# p2_half_bridge.net
KiCad netlist of a schematic drawn in Altium Designer
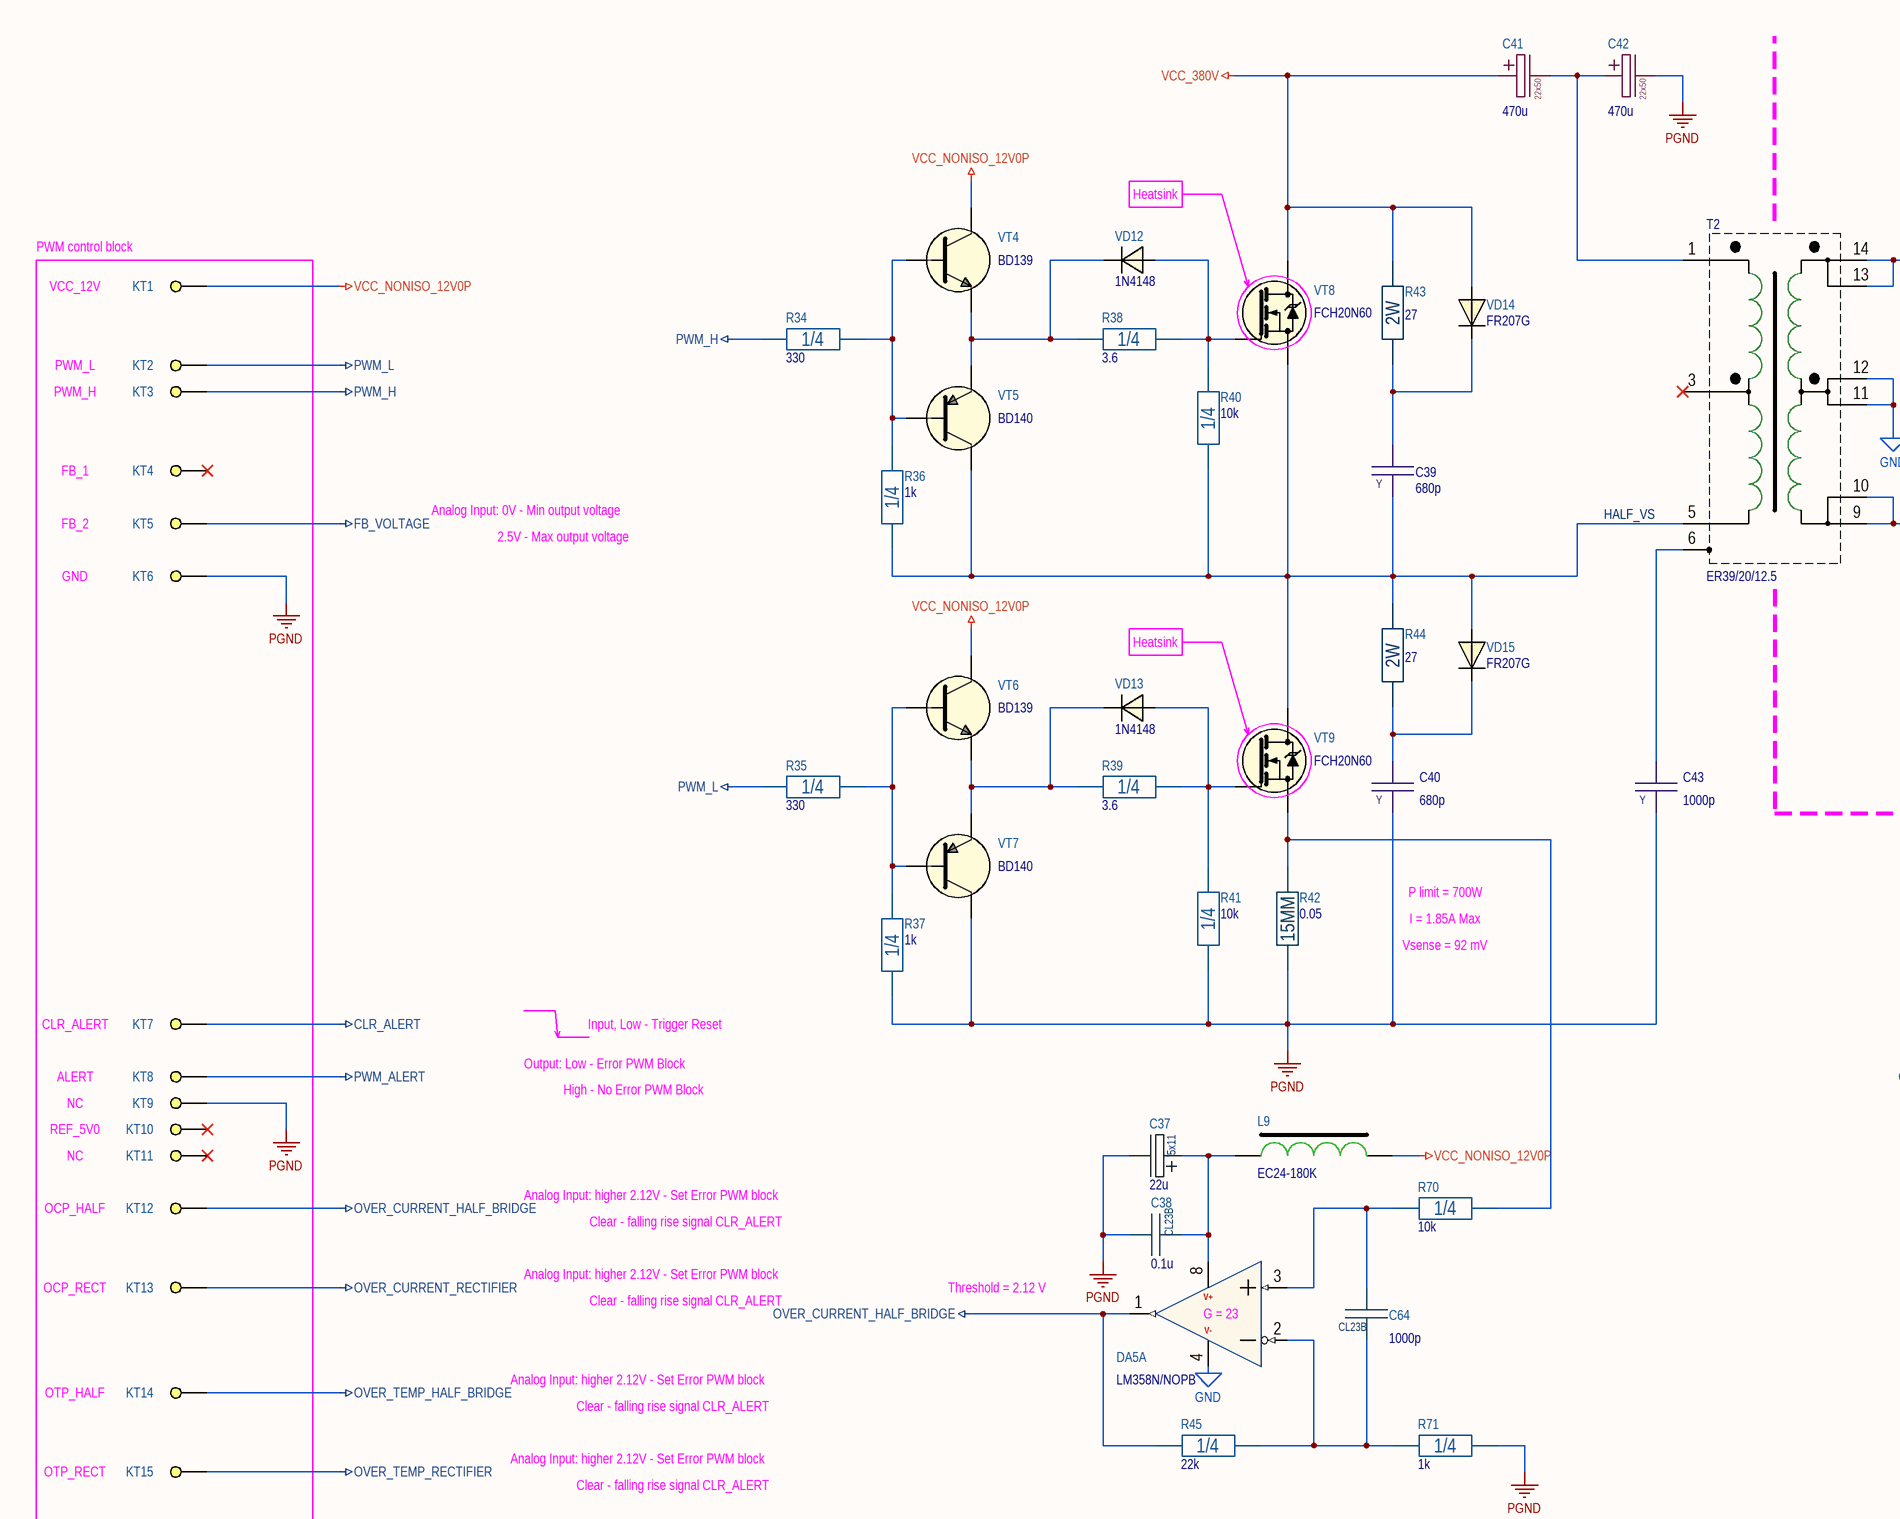
[diagram p0: p2_half_bridge.SchDoc, top left]
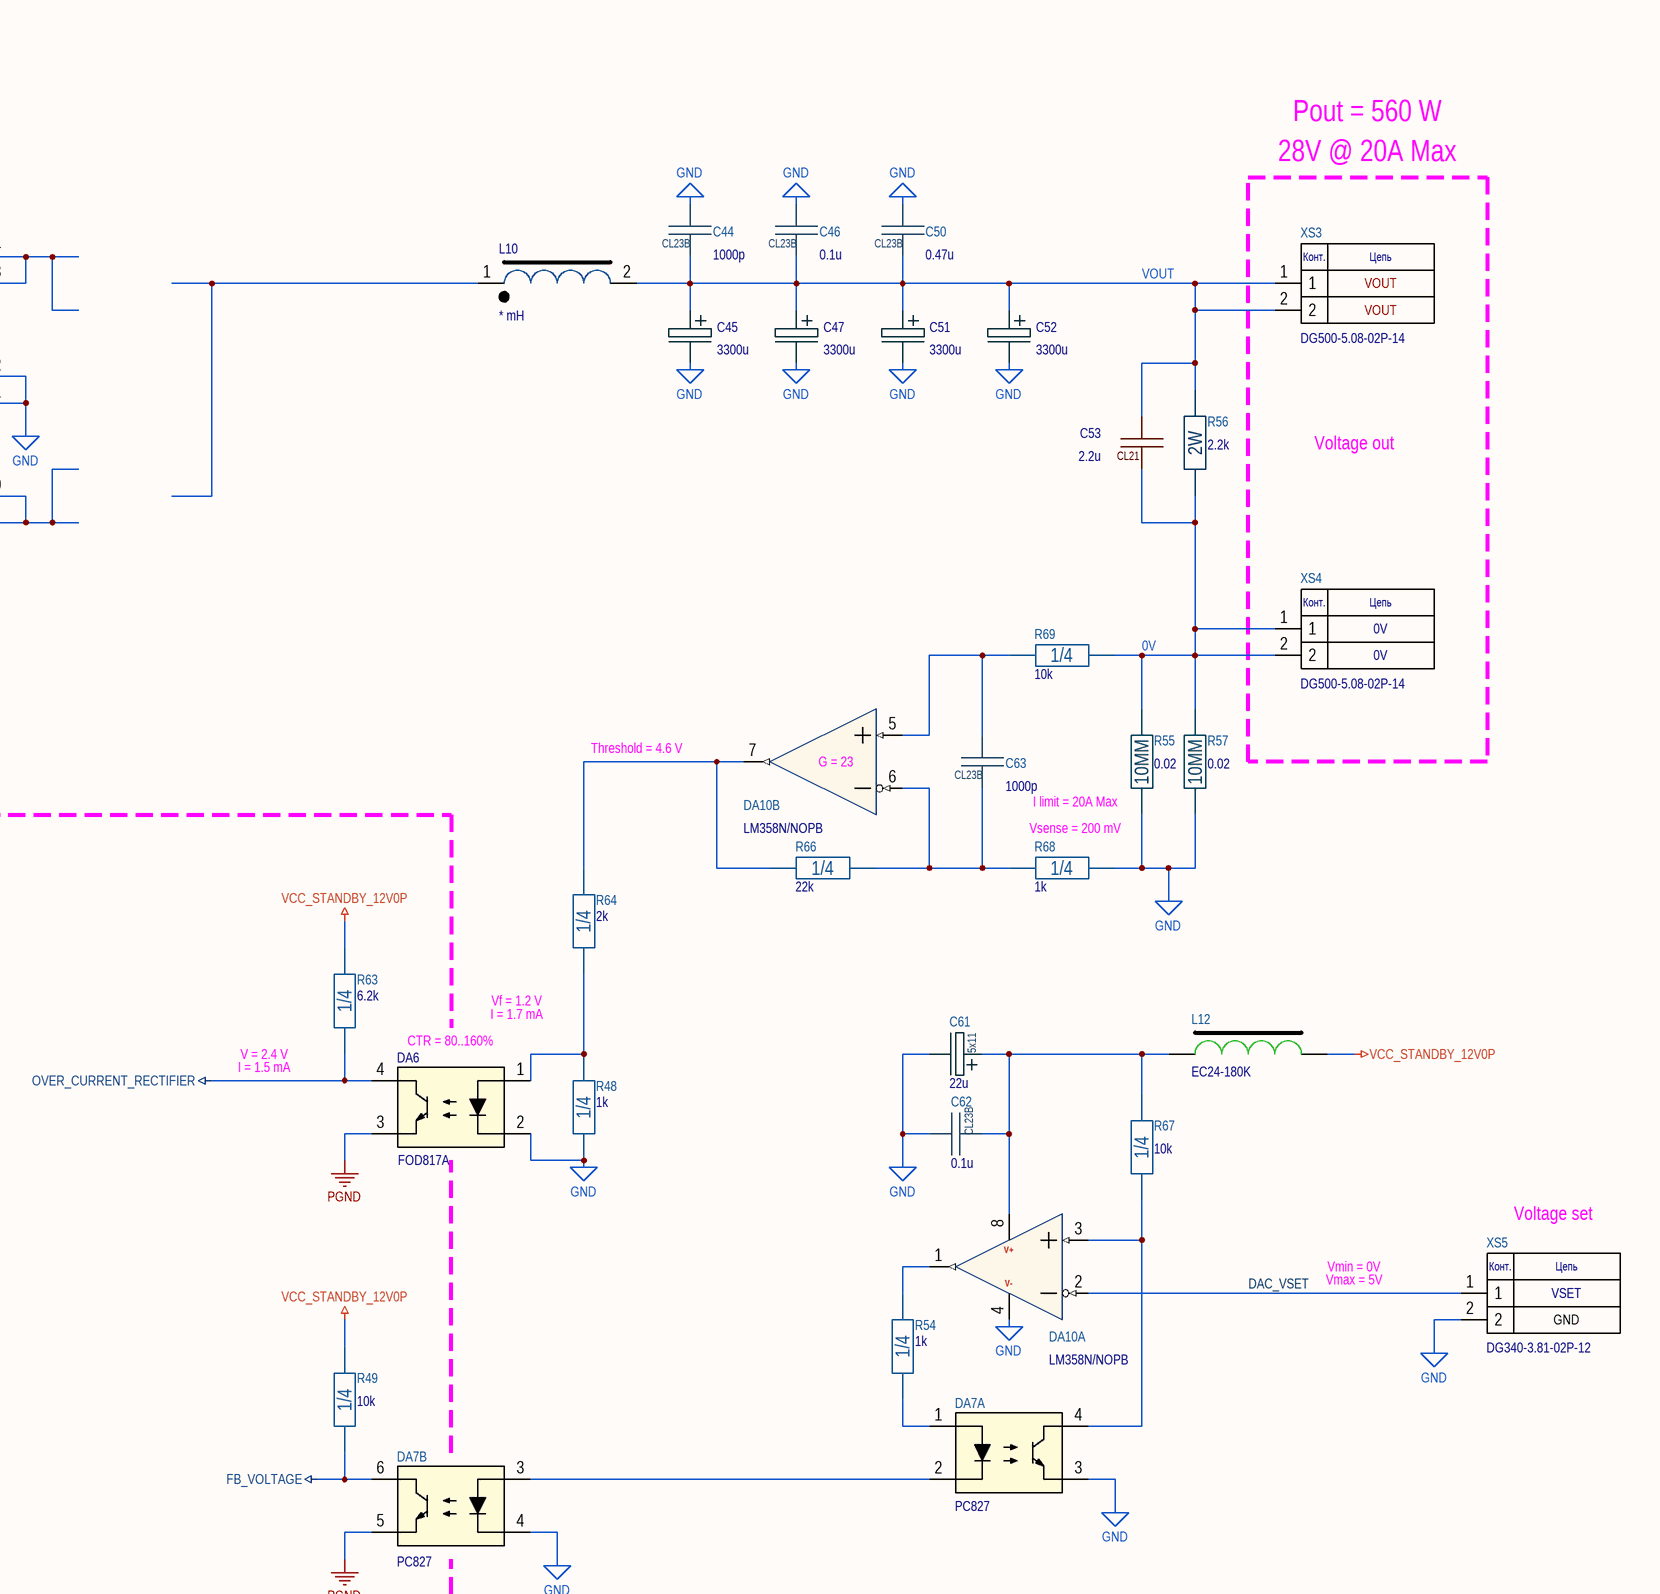
[diagram p1: p2_half_bridge.SchDoc, top right]
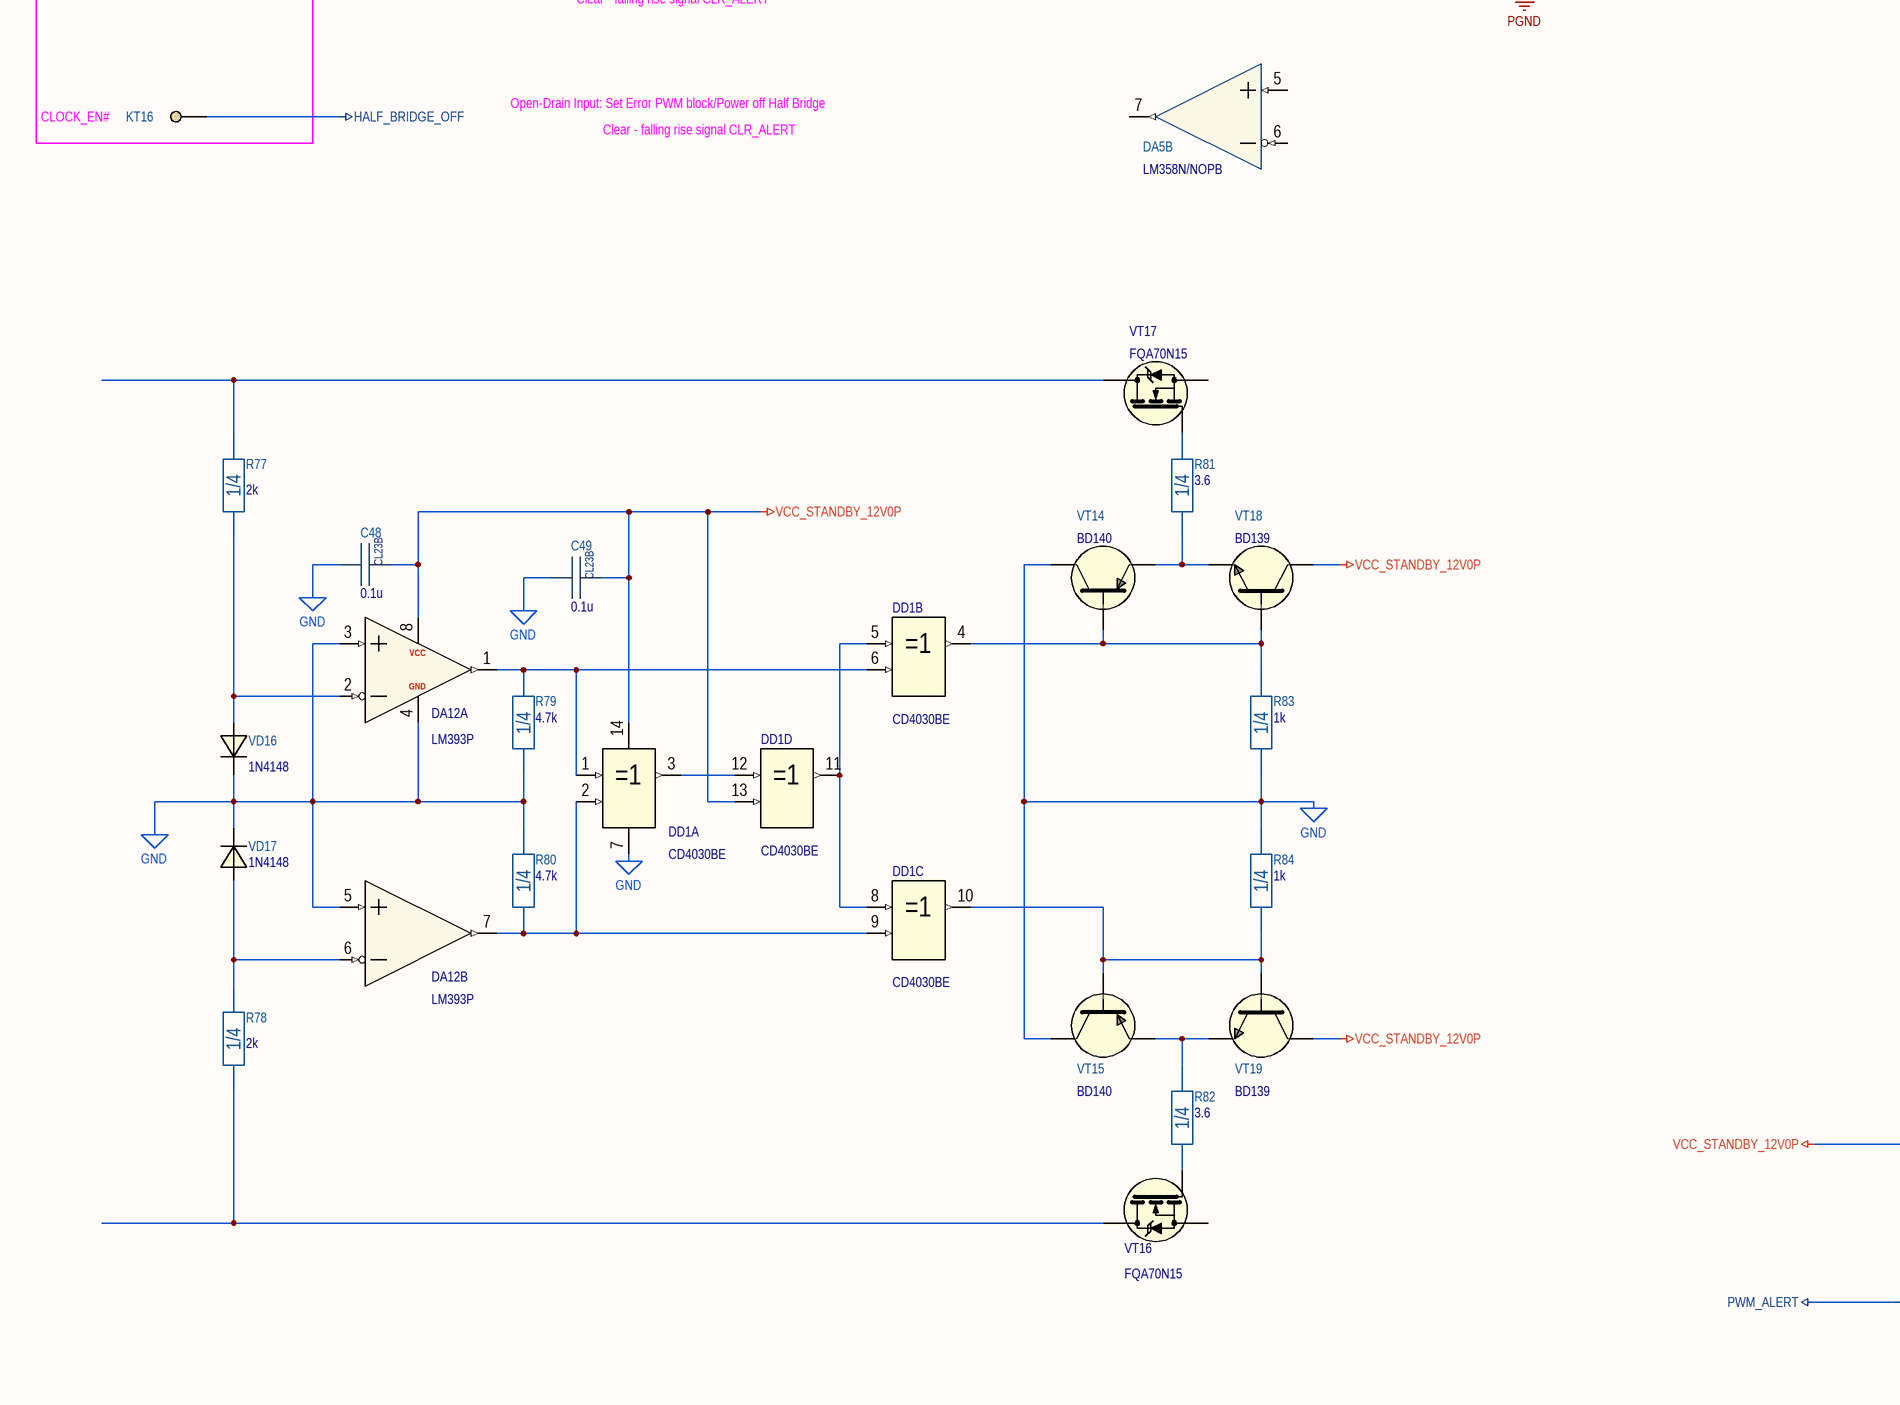
[diagram p2: p2_half_bridge.SchDoc, bottom left]
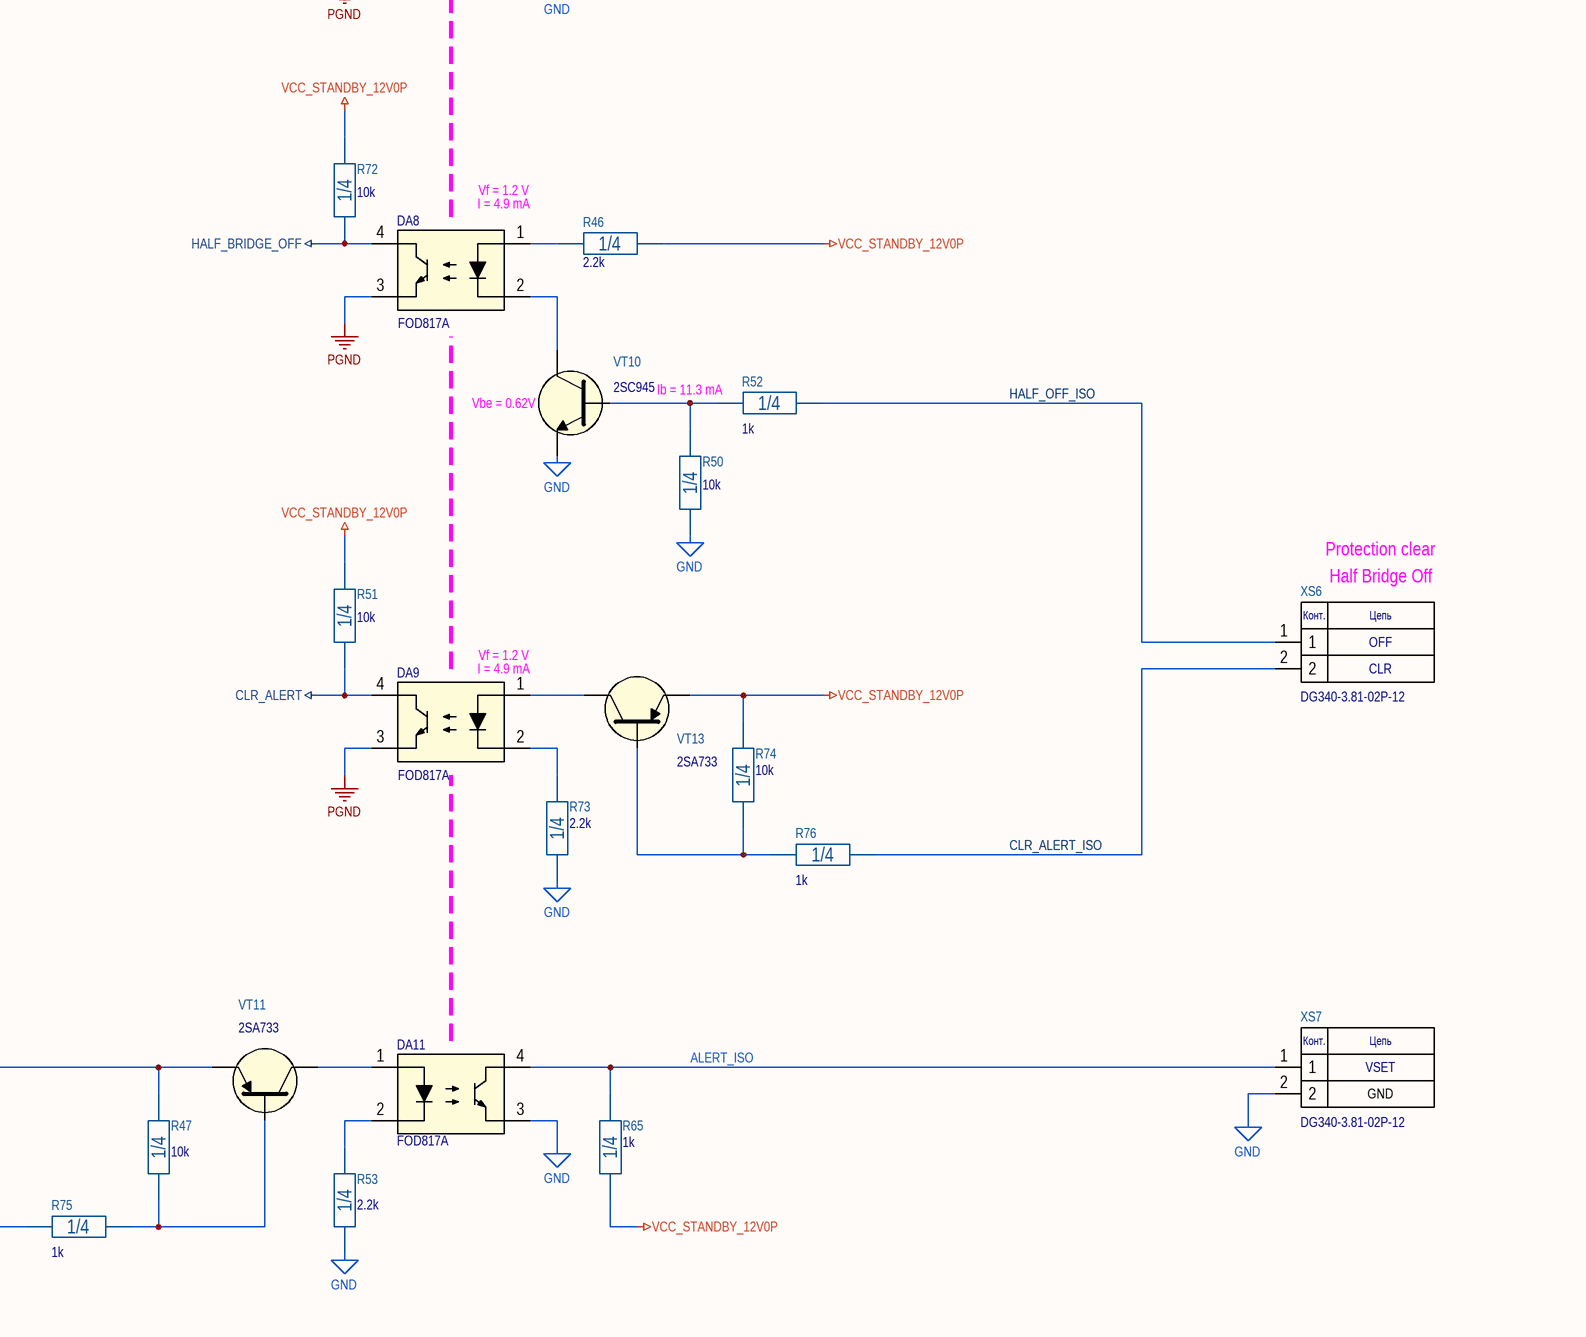
[diagram p3: p2_half_bridge.SchDoc, bottom right]

(export (version "E")
  (design (tool "Eeschema 10.0.6"))
  (components
    (comp (ref "C37")
      (value "22u")
      (footprint "PcbLib_RC:ECAP5X11X2.0_BRW")
      (description "Aluminium capacitor")
      (fields
        (field (name "TOLERANCE") "± 20 %")
        (field (name "VOLTAGE") "63V")
        (field (name "PACKAGE") "5x11")
      )
      (libsource (lib "Schlib_RC") (part "C_ECAP"))
    )
    (comp (ref "C38")
      (value "0.1u")
      (footprint "PcbLib_RC:CL23B_7.2x2.5")
      (description "Box-type metallized polyester film capacitor")
      (fields
        (field (name "TOLERANCE") "± * %")
        (field (name "VOLTAGE") "63V")
        (field (name "PACKAGE") "CL23B")
      )
      (libsource (lib "Schlib_RC") (part "CL23B"))
    )
    (comp (ref "C39")
      (value "680p")
      (footprint "PcbLib_RC:JYC_Y2_CAP_7.5")
      (description "High Voltage Ceramic Capacitor")
      (fields
        (field (name "TOLERANCE") "± 10 %")
        (field (name "VOLTAGE") "2000V")
        (field (name "PACKAGE") "Y")
      )
      (libsource (lib "Schlib_RC") (part "JB_Y2"))
    )
    (comp (ref "C40")
      (value "680p")
      (footprint "PcbLib_RC:JYC_Y2_CAP_7.5")
      (description "High Voltage Ceramic Capacitor")
      (fields
        (field (name "TOLERANCE") "± 10 %")
        (field (name "VOLTAGE") "2000V")
        (field (name "PACKAGE") "Y")
      )
      (libsource (lib "Schlib_RC") (part "JB_Y2"))
    )
    (comp (ref "C41")
      (value "470u")
      (footprint "PcbLib_RC:ECAP22X50X10")
      (description "Aluminium capacitors 35x50mm")
      (fields
        (field (name "TOLERANCE") "± 20 %")
        (field (name "VOLTAGE") "200V")
        (field (name "PACKAGE") "22x50")
      )
      (libsource (lib "Schlib_RC") (part "ECAP_22x50"))
    )
    (comp (ref "C42")
      (value "470u")
      (footprint "PcbLib_RC:ECAP22X50X10")
      (description "Aluminium capacitors 35x50mm")
      (fields
        (field (name "TOLERANCE") "± 20 %")
        (field (name "VOLTAGE") "200V")
        (field (name "PACKAGE") "22x50")
      )
      (libsource (lib "Schlib_RC") (part "ECAP_22x50"))
    )
    (comp (ref "C43")
      (value "1000p")
      (footprint "PcbLib_RC:JYC_Y2_CAP_7.5")
      (description "High Voltage Ceramic Capacitor")
      (fields
        (field (name "TOLERANCE") "± 20 %")
        (field (name "VOLTAGE") "2000V")
        (field (name "PACKAGE") "Y")
      )
      (libsource (lib "Schlib_RC") (part "JB_Y2"))
    )
    (comp (ref "C44")
      (value "1000p")
      (footprint "PcbLib_RC:CL23B_7.2x2.5")
      (description "Box-type metallized polyester film capacitor")
      (fields
        (field (name "TOLERANCE") "± * %")
        (field (name "VOLTAGE") "63V")
        (field (name "PACKAGE") "CL23B")
      )
      (libsource (lib "Schlib_RC") (part "CL23B"))
    )
    (comp (ref "C45")
      (value "3300u")
      (footprint "PcbLib_RC:ECAP16X36X75_BLK")
      (description "Aluminium capacitor")
      (fields (field (name "TOLERANCE") "± 20 %") (field (name "VOLTAGE") "50V"))
      (libsource (lib "Schlib_RC") (part "C_ECAP"))
    )
    (comp (ref "C46")
      (value "0.1u")
      (footprint "PcbLib_RC:CL23B_7.2x2.5")
      (description "Box-type metallized polyester film capacitor")
      (fields
        (field (name "TOLERANCE") "± * %")
        (field (name "VOLTAGE") "63V")
        (field (name "PACKAGE") "CL23B")
      )
      (libsource (lib "Schlib_RC") (part "CL23B"))
    )
    (comp (ref "C47")
      (value "3300u")
      (footprint "PcbLib_RC:ECAP16X36X75_BLK")
      (description "Aluminium capacitor")
      (fields (field (name "TOLERANCE") "± 20 %") (field (name "VOLTAGE") "50V"))
      (libsource (lib "Schlib_RC") (part "C_ECAP"))
    )
    (comp (ref "C48")
      (value "0.1u")
      (footprint "PcbLib_RC:CL23B_7.2x2.5")
      (description "Box-type metallized polyester film capacitor")
      (fields
        (field (name "TOLERANCE") "± * %")
        (field (name "VOLTAGE") "63V")
        (field (name "PACKAGE") "CL23B")
      )
      (libsource (lib "Schlib_RC") (part "CL23B"))
    )
    (comp (ref "C49")
      (value "0.1u")
      (footprint "PcbLib_RC:CL23B_7.2x2.5")
      (description "Box-type metallized polyester film capacitor")
      (fields
        (field (name "TOLERANCE") "± * %")
        (field (name "VOLTAGE") "63V")
        (field (name "PACKAGE") "CL23B")
      )
      (libsource (lib "Schlib_RC") (part "CL23B"))
    )
    (comp (ref "C50")
      (value "0.47u")
      (footprint "PcbLib_RC:CL23B_7.2x3.5")
      (description "Box-type metallized polyester film capacitor")
      (fields
        (field (name "TOLERANCE") "± * %")
        (field (name "VOLTAGE") "63V")
        (field (name "PACKAGE") "CL23B")
      )
      (libsource (lib "Schlib_RC") (part "CL23B"))
    )
    (comp (ref "C51")
      (value "3300u")
      (footprint "PcbLib_RC:ECAP16X36X75_BLK")
      (description "Aluminium capacitor")
      (fields (field (name "TOLERANCE") "± 20 %") (field (name "VOLTAGE") "50V"))
      (libsource (lib "Schlib_RC") (part "C_ECAP"))
    )
    (comp (ref "C52")
      (value "3300u")
      (footprint "PcbLib_RC:ECAP16X36X75_BLK")
      (description "Aluminium capacitor")
      (fields (field (name "TOLERANCE") "± 20 %") (field (name "VOLTAGE") "50V"))
      (libsource (lib "Schlib_RC") (part "C_ECAP"))
    )
    (comp (ref "C53")
      (value "2.2u")
      (footprint "PcbLib_RC:CL21_29x24.5x14.0_P27.5")
      (description "CL21 Type Metallized Polyester Film Capacitor")
      (fields
        (field (name "TOLERANCE") "± * %")
        (field (name "VOLTAGE") "250V")
        (field (name "PACKAGE") "CL21")
      )
      (libsource (lib "Schlib_RC") (part "CL21"))
    )
    (comp (ref "C61")
      (value "22u")
      (footprint "PcbLib_RC:ECAP5X11X2.0_BRW")
      (description "Aluminium capacitor")
      (fields
        (field (name "TOLERANCE") "± 20 %")
        (field (name "VOLTAGE") "63V")
        (field (name "PACKAGE") "5x11")
      )
      (libsource (lib "Schlib_RC") (part "C_ECAP"))
    )
    (comp (ref "C62")
      (value "0.1u")
      (footprint "PcbLib_RC:CL23B_7.2x2.5")
      (description "Box-type metallized polyester film capacitor")
      (fields
        (field (name "TOLERANCE") "± * %")
        (field (name "VOLTAGE") "63V")
        (field (name "PACKAGE") "CL23B")
      )
      (libsource (lib "Schlib_RC") (part "CL23B"))
    )
    (comp (ref "C63")
      (value "1000p")
      (footprint "PcbLib_RC:CL23B_7.2x2.5")
      (description "Box-type metallized polyester film capacitor")
      (fields
        (field (name "TOLERANCE") "± * %")
        (field (name "VOLTAGE") "63V")
        (field (name "PACKAGE") "CL23B")
      )
      (libsource (lib "Schlib_RC") (part "CL23B"))
    )
    (comp (ref "C64")
      (value "1000p")
      (footprint "PcbLib_RC:CL23B_7.2x2.5")
      (description "Box-type metallized polyester film capacitor")
      (fields
        (field (name "TOLERANCE") "± * %")
        (field (name "VOLTAGE") "63V")
        (field (name "PACKAGE") "CL23B")
      )
      (libsource (lib "Schlib_RC") (part "CL23B"))
    )
    (comp (ref "DA5")
      (value "LM358N/NOPB")
      (footprint "PcbLib_ICs:DIP-8P-M01_with_SO8")
      (description "Low-Power, Dual-Operational Amplifiers")
      (fields (field (name "MANUFACTURER") "Texas Instruments"))
      (libsource (lib "Schlib_Texas_Instruments") (part "LM358N/NOPB"))
    )
    (comp (ref "DA6")
      (value "FOD817A")
      (footprint "PcbLib_ICs:DIP-4P")
      (description "5kV Phototransistor Optocoupler")
      (fields (field (name "MANUFACTURER") "ON Semiconductor"))
      (libsource (lib "") (part "FOD817A_1"))
    )
    (comp (ref "DA7")
      (value "PC827")
      (footprint "PcbLib_ICs:DIP-8P-M01")
      (description "High Density Mounting Type\r\nPhotocoupler")
      (fields (field (name "MANUFACTURER") "Sharp"))
      (libsource (lib "Schlib_OtherComponents") (part "PC827"))
    )
    (comp (ref "DA8")
      (value "FOD817A")
      (footprint "PcbLib_ICs:DIP-4P")
      (description "5kV Phototransistor Optocoupler")
      (fields (field (name "MANUFACTURER") "ON Semiconductor"))
      (libsource (lib "") (part "FOD817A_1"))
    )
    (comp (ref "DA9")
      (value "FOD817A")
      (footprint "PcbLib_ICs:DIP-4P")
      (description "5kV Phototransistor Optocoupler")
      (fields (field (name "MANUFACTURER") "ON Semiconductor"))
      (libsource (lib "") (part "FOD817A_1"))
    )
    (comp (ref "DA10")
      (value "LM358N/NOPB")
      (footprint "PcbLib_ICs:DIP-8P-M01_with_SO8")
      (description "Low-Power, Dual-Operational Amplifiers")
      (fields (field (name "MANUFACTURER") "Texas Instruments"))
      (libsource (lib "Schlib_Texas_Instruments") (part "LM358N/NOPB"))
    )
    (comp (ref "DA11")
      (value "FOD817A")
      (footprint "PcbLib_ICs:DIP-4P")
      (description "5kV Phototransistor Optocoupler")
      (fields (field (name "MANUFACTURER") "ON Semiconductor"))
      (libsource (lib "Schlib_ONSemiconductor") (part "FOD817A"))
    )
    (comp (ref "DA12")
      (value "LM393P")
      (footprint "PcbLib_ICs:DIP-8P-M01_with_SO8")
      (description "Dual Comparator")
      (fields (field (name "MANUFACTURER") "Texas Instruments"))
      (libsource (lib "Schlib_Texas_Instruments") (part "LM393P"))
    )
    (comp (ref "DD1")
      (value "CD4030BE")
      (footprint "PcbLib_ICs:DIP-14P-M02")
      (description "Quad XOR-Gate")
      (fields (field (name "MANUFACTURER") "Texas Instruments"))
      (libsource (lib "Schlib_Texas_Instruments") (part "CD4030BE"))
    )
    (comp (ref "KT1")
      (value "TEST_PAD")
      (footprint "PcbLib_Others:TEST_PAD_HOLE1.1x1.8SQ")
      (description "Test pad")
      (libsource (lib "Schlib_OtherComponents") (part "TEST_PAD"))
    )
    (comp (ref "KT2")
      (value "TEST_PAD")
      (footprint "PcbLib_Others:TEST_PAD_HOLE1.1x1.8")
      (description "Test pad")
      (libsource (lib "Schlib_OtherComponents") (part "TEST_PAD"))
    )
    (comp (ref "KT3")
      (value "TEST_PAD")
      (footprint "PcbLib_Others:TEST_PAD_HOLE1.1x1.8")
      (description "Test pad")
      (libsource (lib "Schlib_OtherComponents") (part "TEST_PAD"))
    )
    (comp (ref "KT4")
      (value "TEST_PAD")
      (footprint "PcbLib_Others:TEST_PAD_HOLE1.1x1.8")
      (description "Test pad")
      (libsource (lib "Schlib_OtherComponents") (part "TEST_PAD"))
    )
    (comp (ref "KT5")
      (value "TEST_PAD")
      (footprint "PcbLib_Others:TEST_PAD_HOLE1.1x1.8")
      (description "Test pad")
      (libsource (lib "Schlib_OtherComponents") (part "TEST_PAD"))
    )
    (comp (ref "KT6")
      (value "TEST_PAD")
      (footprint "PcbLib_Others:TEST_PAD_HOLE1.1x1.8")
      (description "Test pad")
      (libsource (lib "Schlib_OtherComponents") (part "TEST_PAD"))
    )
    (comp (ref "KT7")
      (value "TEST_PAD")
      (footprint "PcbLib_Others:TEST_PAD_HOLE1.1x1.8")
      (description "Test pad")
      (libsource (lib "Schlib_OtherComponents") (part "TEST_PAD"))
    )
    (comp (ref "KT8")
      (value "TEST_PAD")
      (footprint "PcbLib_Others:TEST_PAD_HOLE1.1x1.8")
      (description "Test pad")
      (libsource (lib "Schlib_OtherComponents") (part "TEST_PAD"))
    )
    (comp (ref "KT9")
      (value "TEST_PAD")
      (footprint "PcbLib_Others:TEST_PAD_HOLE1.1x1.8")
      (description "Test pad")
      (libsource (lib "Schlib_OtherComponents") (part "TEST_PAD"))
    )
    (comp (ref "KT10")
      (value "TEST_PAD")
      (footprint "PcbLib_Others:TEST_PAD_HOLE1.1x1.8")
      (description "Test pad")
      (libsource (lib "Schlib_OtherComponents") (part "TEST_PAD"))
    )
    (comp (ref "KT11")
      (value "TEST_PAD")
      (footprint "PcbLib_Others:TEST_PAD_HOLE1.1x1.8")
      (description "Test pad")
      (libsource (lib "Schlib_OtherComponents") (part "TEST_PAD"))
    )
    (comp (ref "KT12")
      (value "TEST_PAD")
      (footprint "PcbLib_Others:TEST_PAD_HOLE1.1x1.8")
      (description "Test pad")
      (libsource (lib "Schlib_OtherComponents") (part "TEST_PAD"))
    )
    (comp (ref "KT13")
      (value "TEST_PAD")
      (footprint "PcbLib_Others:TEST_PAD_HOLE1.1x1.8")
      (description "Test pad")
      (libsource (lib "Schlib_OtherComponents") (part "TEST_PAD"))
    )
    (comp (ref "KT14")
      (value "TEST_PAD")
      (footprint "PcbLib_Others:TEST_PAD_HOLE1.1x1.8")
      (description "Test pad")
      (libsource (lib "Schlib_OtherComponents") (part "TEST_PAD"))
    )
    (comp (ref "KT15")
      (value "TEST_PAD")
      (footprint "PcbLib_Others:TEST_PAD_HOLE1.1x1.8")
      (description "Test pad")
      (libsource (lib "Schlib_OtherComponents") (part "TEST_PAD"))
    )
    (comp (ref "KT16")
      (value "TEST_PAD")
      (footprint "PcbLib_Others:TEST_PAD_HOLE1.1x1.8")
      (description "Test pad")
      (libsource (lib "Schlib_OtherComponents") (part "TEST_PAD"))
    )
    (comp (ref "L9")
      (value "EC24-180K")
      (footprint "PcbLib_RC:EC24_GREEN")
      (description "Axial leaded coated inductors")
      (fields (field (name "MANUFACTURER") "3L Electronic"))
      (libsource (lib "Schlib_RC") (part "EC24"))
    )
    (comp (ref "L10")
      (value "* mH")
      (footprint "PcbLib_RC:CORE_D33_GB")
      (description "Ferrite Core D32.8/20.1/10.7 mm")
      (libsource (lib "Schlib_OtherComponents") (part "CORE_D33"))
    )
    (comp (ref "L12")
      (value "EC24-180K")
      (footprint "PcbLib_RC:EC24_GREEN")
      (description "Axial leaded coated inductors")
      (fields (field (name "MANUFACTURER") "3L Electronic"))
      (libsource (lib "Schlib_RC") (part "EC24"))
    )
    (comp (ref "R34")
      (value "330")
      (footprint "PcbLib_RC:CFR-25(VERTICAL)")
      (description "Resistor 1/4W")
      (fields
        (field (name "TOLERANCE") "± 1 %")
        (field (name "PART NUMBER") "MFR-25FTF52-330R")
        (field (name "PACKAGE") "1/4")
      )
      (libsource (lib "Schlib_RC") (part "CF25"))
    )
    (comp (ref "R35")
      (value "330")
      (footprint "PcbLib_RC:CFR-25(VERTICAL)")
      (description "Resistor 1/4W")
      (fields
        (field (name "TOLERANCE") "± 1 %")
        (field (name "PART NUMBER") "MFR-25FTF52-330R")
        (field (name "PACKAGE") "1/4")
      )
      (libsource (lib "Schlib_RC") (part "CF25"))
    )
    (comp (ref "R36")
      (value "1k")
      (footprint "PcbLib_RC:CFR-25(VERTICAL)")
      (description "Resistor 1/4W")
      (fields
        (field (name "TOLERANCE") "± 1 %")
        (field (name "PART NUMBER") "MFR-25FTF52-1K")
        (field (name "PACKAGE") "1/4")
      )
      (libsource (lib "Schlib_RC") (part "CF25"))
    )
    (comp (ref "R37")
      (value "1k")
      (footprint "PcbLib_RC:CFR-25(VERTICAL)")
      (description "Resistor 1/4W")
      (fields
        (field (name "TOLERANCE") "± 1 %")
        (field (name "PART NUMBER") "MFR-25FTF52-1K")
        (field (name "PACKAGE") "1/4")
      )
      (libsource (lib "Schlib_RC") (part "CF25"))
    )
    (comp (ref "R38")
      (value "3.6")
      (footprint "PcbLib_RC:CFR-25(VERTICAL)")
      (description "Resistor 1/4W")
      (fields
        (field (name "TOLERANCE") "± 1 %")
        (field (name "PART NUMBER") "MFR-25FTF52-3R6")
        (field (name "PACKAGE") "1/4")
      )
      (libsource (lib "Schlib_RC") (part "CF25"))
    )
    (comp (ref "R39")
      (value "3.6")
      (footprint "PcbLib_RC:CFR-25(VERTICAL)")
      (description "Resistor 1/4W")
      (fields
        (field (name "TOLERANCE") "± 1 %")
        (field (name "PART NUMBER") "MFR-25FTF52-3R6")
        (field (name "PACKAGE") "1/4")
      )
      (libsource (lib "Schlib_RC") (part "CF25"))
    )
    (comp (ref "R40")
      (value "10k")
      (footprint "PcbLib_RC:CFR-25(VERTICAL)")
      (description "Resistor 1/4W")
      (fields
        (field (name "TOLERANCE") "± 1 %")
        (field (name "PART NUMBER") "MFR-25FTF52-10K")
        (field (name "PACKAGE") "1/4")
      )
      (libsource (lib "Schlib_RC") (part "CF25"))
    )
    (comp (ref "R41")
      (value "10k")
      (footprint "PcbLib_RC:CFR-25(VERTICAL)")
      (description "Resistor 1/4W")
      (fields
        (field (name "TOLERANCE") "± 1 %")
        (field (name "PART NUMBER") "MFR-25FTF52-10K")
        (field (name "PACKAGE") "1/4")
      )
      (libsource (lib "Schlib_RC") (part "CF25"))
    )
    (comp (ref "R42")
      (value "0.05")
      (footprint "PcbLib_RC:CURRENT_SENSE_15x18mm")
      (description "Constantan shunt resistor, pitch = 15mm")
      (fields (field (name "TOLERANCE") "±  %") (field (name "PACKAGE") "15MM"))
      (libsource (lib "Schlib_RC") (part "SHUNT_15MM"))
    )
    (comp (ref "R43")
      (value "27")
      (footprint "PcbLib_RC:CFR-200(VERTICAL)")
      (description "Resistor 2W")
      (fields
        (field (name "TOLERANCE") "± 5 %")
        (field (name "PART NUMBER") "KNP200JB-73-27R")
        (field (name "PACKAGE") "2W")
      )
      (libsource (lib "Schlib_RC") (part "CF200"))
    )
    (comp (ref "R44")
      (value "27")
      (footprint "PcbLib_RC:CFR-200(VERTICAL)")
      (description "Resistor 2W")
      (fields
        (field (name "TOLERANCE") "± 5 %")
        (field (name "PART NUMBER") "KNP200JB-73-27R")
        (field (name "PACKAGE") "2W")
      )
      (libsource (lib "Schlib_RC") (part "CF200"))
    )
    (comp (ref "R45")
      (value "22k")
      (footprint "PcbLib_RC:CFR-25")
      (description "Resistor 1/4W")
      (fields
        (field (name "TOLERANCE") "± 1 %")
        (field (name "PART NUMBER") "MFR-25FTF52-22K")
        (field (name "PACKAGE") "1/4")
      )
      (libsource (lib "Schlib_RC") (part "CF25"))
    )
    (comp (ref "R46")
      (value "2.2k")
      (footprint "PcbLib_RC:CFR-25")
      (description "Resistor 1/4W")
      (fields
        (field (name "TOLERANCE") "± 1 %")
        (field (name "PART NUMBER") "MFR-25FTF52-2K2")
        (field (name "PACKAGE") "1/4")
      )
      (libsource (lib "Schlib_RC") (part "CF25"))
    )
    (comp (ref "R47")
      (value "10k")
      (footprint "PcbLib_RC:CFR-25")
      (description "Resistor 1/4W")
      (fields
        (field (name "TOLERANCE") "± 1 %")
        (field (name "PART NUMBER") "MFR-25FTF52-10K")
        (field (name "PACKAGE") "1/4")
      )
      (libsource (lib "Schlib_RC") (part "CF25"))
    )
    (comp (ref "R48")
      (value "1k")
      (footprint "PcbLib_RC:CFR-25")
      (description "Resistor 1/4W")
      (fields
        (field (name "TOLERANCE") "± 1 %")
        (field (name "PART NUMBER") "MFR-25FTF52-1K")
        (field (name "PACKAGE") "1/4")
      )
      (libsource (lib "Schlib_RC") (part "CF25"))
    )
    (comp (ref "R49")
      (value "10k")
      (footprint "PcbLib_RC:CFR-25")
      (description "Resistor 1/4W")
      (fields
        (field (name "TOLERANCE") "± 1 %")
        (field (name "PART NUMBER") "MFR-25FTF52-10K")
        (field (name "PACKAGE") "1/4")
      )
      (libsource (lib "Schlib_RC") (part "CF25"))
    )
    (comp (ref "R50")
      (value "10k")
      (footprint "PcbLib_RC:CFR-25")
      (description "Resistor 1/4W")
      (fields
        (field (name "TOLERANCE") "± 1 %")
        (field (name "PART NUMBER") "MFR-25FTF52-10K")
        (field (name "PACKAGE") "1/4")
      )
      (libsource (lib "Schlib_RC") (part "CF25"))
    )
    (comp (ref "R51")
      (value "10k")
      (footprint "PcbLib_RC:CFR-25")
      (description "Resistor 1/4W")
      (fields
        (field (name "TOLERANCE") "± 1 %")
        (field (name "PART NUMBER") "MFR-25FTF52-10K")
        (field (name "PACKAGE") "1/4")
      )
      (libsource (lib "Schlib_RC") (part "CF25"))
    )
    (comp (ref "R52")
      (value "1k")
      (footprint "PcbLib_RC:CFR-25")
      (description "Resistor 1/4W")
      (fields
        (field (name "TOLERANCE") "± 1 %")
        (field (name "PART NUMBER") "MFR-25FTF52-1K")
        (field (name "PACKAGE") "1/4")
      )
      (libsource (lib "Schlib_RC") (part "CF25"))
    )
    (comp (ref "R53")
      (value "2.2k")
      (footprint "PcbLib_RC:CFR-25")
      (description "Resistor 1/4W")
      (fields
        (field (name "TOLERANCE") "± 1 %")
        (field (name "PART NUMBER") "MFR-25FTF52-2K2")
        (field (name "PACKAGE") "1/4")
      )
      (libsource (lib "Schlib_RC") (part "CF25"))
    )
    (comp (ref "R54")
      (value "1k")
      (footprint "PcbLib_RC:CFR-25")
      (description "Resistor 1/4W")
      (fields
        (field (name "TOLERANCE") "± 1 %")
        (field (name "PART NUMBER") "MFR-25FTF52-1K")
        (field (name "PACKAGE") "1/4")
      )
      (libsource (lib "Schlib_RC") (part "CF25"))
    )
    (comp (ref "R55")
      (value "0.02")
      (footprint "PcbLib_RC:CURRENT_SENSE_10x11mm")
      (description "Constantan shunt resistor, pitch = 10mm")
      (fields (field (name "TOLERANCE") "± 5 %") (field (name "PACKAGE") "10MM"))
      (libsource (lib "Schlib_RC") (part "SHUNT_10MM"))
    )
    (comp (ref "R56")
      (value "2.2k")
      (footprint "PcbLib_RC:CFR-200(VERTICAL)")
      (description "Resistor 2W")
      (fields
        (field (name "TOLERANCE") "± 5 %")
        (field (name "PART NUMBER") "KNP200JB-73-2K2")
        (field (name "PACKAGE") "2W")
      )
      (libsource (lib "Schlib_RC") (part "CF200"))
    )
    (comp (ref "R57")
      (value "0.02")
      (footprint "PcbLib_RC:CURRENT_SENSE_10x11mm")
      (description "Constantan shunt resistor, pitch = 10mm")
      (fields (field (name "TOLERANCE") "± 5 %") (field (name "PACKAGE") "10MM"))
      (libsource (lib "Schlib_RC") (part "SHUNT_10MM"))
    )
    (comp (ref "R63")
      (value "6.2k")
      (footprint "PcbLib_RC:CFR-25")
      (description "Resistor 1/4W")
      (fields
        (field (name "TOLERANCE") "± 1 %")
        (field (name "PART NUMBER") "MFR-25FTF52-5.1K")
        (field (name "PACKAGE") "1/4")
      )
      (libsource (lib "Schlib_RC") (part "CF25"))
    )
    (comp (ref "R64")
      (value "2k")
      (footprint "PcbLib_RC:CFR-25")
      (description "Resistor 1/4W")
      (fields
        (field (name "TOLERANCE") "± 1 %")
        (field (name "PART NUMBER") "MFR-25FTF52-2K")
        (field (name "PACKAGE") "1/4")
      )
      (libsource (lib "Schlib_RC") (part "CF25"))
    )
    (comp (ref "R65")
      (value "1k")
      (footprint "PcbLib_RC:CFR-25")
      (description "Resistor 1/4W")
      (fields
        (field (name "TOLERANCE") "± 1 %")
        (field (name "PART NUMBER") "MFR-25FTF52-1K")
        (field (name "PACKAGE") "1/4")
      )
      (libsource (lib "Schlib_RC") (part "CF25"))
    )
    (comp (ref "R66")
      (value "22k")
      (footprint "PcbLib_RC:CFR-25")
      (description "Resistor 1/4W")
      (fields
        (field (name "TOLERANCE") "± 1 %")
        (field (name "PART NUMBER") "MFR-25FTF52-22K")
        (field (name "PACKAGE") "1/4")
      )
      (libsource (lib "Schlib_RC") (part "CF25"))
    )
    (comp (ref "R67")
      (value "10k")
      (footprint "PcbLib_RC:CFR-25")
      (description "Resistor 1/4W")
      (fields
        (field (name "TOLERANCE") "± 1 %")
        (field (name "PART NUMBER") "MFR-25FTF52-10K")
        (field (name "PACKAGE") "1/4")
      )
      (libsource (lib "Schlib_RC") (part "CF25"))
    )
    (comp (ref "R68")
      (value "1k")
      (footprint "PcbLib_RC:CFR-25")
      (description "Resistor 1/4W")
      (fields
        (field (name "TOLERANCE") "± 1 %")
        (field (name "PART NUMBER") "MFR-25FTF52-1K")
        (field (name "PACKAGE") "1/4")
      )
      (libsource (lib "Schlib_RC") (part "CF25"))
    )
    (comp (ref "R69")
      (value "10k")
      (footprint "PcbLib_RC:CFR-25")
      (description "Resistor 1/4W")
      (fields
        (field (name "TOLERANCE") "± 1 %")
        (field (name "PART NUMBER") "MFR-25FTF52-10K")
        (field (name "PACKAGE") "1/4")
      )
      (libsource (lib "Schlib_RC") (part "CF25"))
    )
    (comp (ref "R70")
      (value "10k")
      (footprint "PcbLib_RC:CFR-25")
      (description "Resistor 1/4W")
      (fields
        (field (name "TOLERANCE") "± 1 %")
        (field (name "PART NUMBER") "MFR-25FTF52-10K")
        (field (name "PACKAGE") "1/4")
      )
      (libsource (lib "Schlib_RC") (part "CF25"))
    )
    (comp (ref "R71")
      (value "1k")
      (footprint "PcbLib_RC:CFR-25")
      (description "Resistor 1/4W")
      (fields
        (field (name "TOLERANCE") "± 1 %")
        (field (name "PART NUMBER") "MFR-25FTF52-1K")
        (field (name "PACKAGE") "1/4")
      )
      (libsource (lib "Schlib_RC") (part "CF25"))
    )
    (comp (ref "R72")
      (value "10k")
      (footprint "PcbLib_RC:CFR-25")
      (description "Resistor 1/4W")
      (fields
        (field (name "TOLERANCE") "± 1 %")
        (field (name "PART NUMBER") "MFR-25FTF52-10K")
        (field (name "PACKAGE") "1/4")
      )
      (libsource (lib "Schlib_RC") (part "CF25"))
    )
    (comp (ref "R73")
      (value "2.2k")
      (footprint "PcbLib_RC:CFR-25")
      (description "Resistor 1/4W")
      (fields
        (field (name "TOLERANCE") "± 1 %")
        (field (name "PART NUMBER") "MFR-25FTF52-2K2")
        (field (name "PACKAGE") "1/4")
      )
      (libsource (lib "Schlib_RC") (part "CF25"))
    )
    (comp (ref "R74")
      (value "10k")
      (footprint "PcbLib_RC:CFR-25")
      (description "Resistor 1/4W")
      (fields
        (field (name "TOLERANCE") "± 1 %")
        (field (name "PART NUMBER") "MFR-25FTF52-10K")
        (field (name "PACKAGE") "1/4")
      )
      (libsource (lib "Schlib_RC") (part "CF25"))
    )
    (comp (ref "R75")
      (value "1k")
      (footprint "PcbLib_RC:CFR-25")
      (description "Resistor 1/4W")
      (fields
        (field (name "TOLERANCE") "± 1 %")
        (field (name "PART NUMBER") "MFR-25FTF52-1K")
        (field (name "PACKAGE") "1/4")
      )
      (libsource (lib "Schlib_RC") (part "CF25"))
    )
    (comp (ref "R76")
      (value "1k")
      (footprint "PcbLib_RC:CFR-25")
      (description "Resistor 1/4W")
      (fields
        (field (name "TOLERANCE") "± 1 %")
        (field (name "PART NUMBER") "MFR-25FTF52-1K")
        (field (name "PACKAGE") "1/4")
      )
      (libsource (lib "Schlib_RC") (part "CF25"))
    )
    (comp (ref "R77")
      (value "2k")
      (footprint "PcbLib_RC:CFR-25")
      (description "Resistor 1/4W")
      (fields
        (field (name "TOLERANCE") "± 1 %")
        (field (name "PART NUMBER") "MFR-25FTF52-2K")
        (field (name "PACKAGE") "1/4")
      )
      (libsource (lib "Schlib_RC") (part "CF25"))
    )
    (comp (ref "R78")
      (value "2k")
      (footprint "PcbLib_RC:CFR-25")
      (description "Resistor 1/4W")
      (fields
        (field (name "TOLERANCE") "± 1 %")
        (field (name "PART NUMBER") "MFR-25FTF52-2K")
        (field (name "PACKAGE") "1/4")
      )
      (libsource (lib "Schlib_RC") (part "CF25"))
    )
    (comp (ref "R79")
      (value "4.7k")
      (footprint "PcbLib_RC:CFR-25")
      (description "Resistor 1/4W")
      (fields
        (field (name "TOLERANCE") "± 1 %")
        (field (name "PART NUMBER") "MFR-25FTF52-4K7")
        (field (name "PACKAGE") "1/4")
      )
      (libsource (lib "Schlib_RC") (part "CF25"))
    )
    (comp (ref "R80")
      (value "4.7k")
      (footprint "PcbLib_RC:CFR-25")
      (description "Resistor 1/4W")
      (fields
        (field (name "TOLERANCE") "± 1 %")
        (field (name "PART NUMBER") "MFR-25FTF52-4K7")
        (field (name "PACKAGE") "1/4")
      )
      (libsource (lib "Schlib_RC") (part "CF25"))
    )
    (comp (ref "R81")
      (value "3.6")
      (footprint "PcbLib_RC:CFR-25(VERTICAL)")
      (description "Resistor 1/4W")
      (fields
        (field (name "TOLERANCE") "± 1 %")
        (field (name "PART NUMBER") "MFR-25FTF52-3R6")
        (field (name "PACKAGE") "1/4")
      )
      (libsource (lib "Schlib_RC") (part "CF25"))
    )
    (comp (ref "R82")
      (value "3.6")
      (footprint "PcbLib_RC:CFR-25(VERTICAL)")
      (description "Resistor 1/4W")
      (fields
        (field (name "TOLERANCE") "± 1 %")
        (field (name "PART NUMBER") "MFR-25FTF52-3R6")
        (field (name "PACKAGE") "1/4")
      )
      (libsource (lib "Schlib_RC") (part "CF25"))
    )
    (comp (ref "R83")
      (value "1k")
      (footprint "PcbLib_RC:CFR-25(VERTICAL)")
      (description "Resistor 1/4W")
      (fields
        (field (name "TOLERANCE") "± 1 %")
        (field (name "PART NUMBER") "MFR-25FTF52-1K")
        (field (name "PACKAGE") "1/4")
      )
      (libsource (lib "Schlib_RC") (part "CF25"))
    )
    (comp (ref "R84")
      (value "1k")
      (footprint "PcbLib_RC:CFR-25(VERTICAL)")
      (description "Resistor 1/4W")
      (fields
        (field (name "TOLERANCE") "± 1 %")
        (field (name "PART NUMBER") "MFR-25FTF52-1K")
        (field (name "PACKAGE") "1/4")
      )
      (libsource (lib "Schlib_RC") (part "CF25"))
    )
    (comp (ref "T2")
      (value "ER39/20/12.5")
      (footprint "PcbLib_Others:ER39/20/12.5")
      (description "EE39 Ferrite Core, with footprint for ER35, EE33, EI33 etc.")
      (libsource (lib "Schlib_OtherComponents") (part "ER39"))
    )
    (comp (ref "VD12")
      (value "1N4148")
      (footprint "PcbLib_Discrete:DO-35 GLASS LIGHT RED")
      (description "High-speed diode")
      (libsource (lib "Schlib_NXP_Semiconductors") (part "1N4148"))
    )
    (comp (ref "VD13")
      (value "1N4148")
      (footprint "PcbLib_Discrete:DO-35 GLASS LIGHT RED")
      (description "High-speed diode")
      (libsource (lib "Schlib_NXP_Semiconductors") (part "1N4148"))
    )
    (comp (ref "VD14")
      (value "FR207G")
      (footprint "PcbLib_Discrete:DO-15")
      (description "Diode 2A, 1000V Glass Passivated Fast Recovery Rectifiers")
      (fields (field (name "MANUFACTURER") "Taiwan Semiconductor Corporation"))
      (libsource (lib "Schlib_Taiwan_Semiconductor") (part "FR207G"))
    )
    (comp (ref "VD15")
      (value "FR207G")
      (footprint "PcbLib_Discrete:DO-15")
      (description "Diode 2A, 1000V Glass Passivated Fast Recovery Rectifiers")
      (fields (field (name "MANUFACTURER") "Taiwan Semiconductor Corporation"))
      (libsource (lib "Schlib_Taiwan_Semiconductor") (part "FR207G"))
    )
    (comp (ref "VD16")
      (value "1N4148")
      (footprint "PcbLib_Discrete:DO-35 GLASS LIGHT RED")
      (description "High-speed diode")
      (libsource (lib "Schlib_NXP_Semiconductors") (part "1N4148"))
    )
    (comp (ref "VD17")
      (value "1N4148")
      (footprint "PcbLib_Discrete:DO-35 GLASS LIGHT RED")
      (description "High-speed diode")
      (libsource (lib "Schlib_NXP_Semiconductors") (part "1N4148"))
    )
    (comp (ref "VT4")
      (value "BD139")
      (footprint "PcbLib_ICs:TO-126 (VERTICAL)")
      (description "General Purpose n-p-n Transistors")
      (fields (field (name "MANUFACTURER") "STMicroelectronics"))
      (libsource (lib "Schlib_STMicroelectronics") (part "BD139"))
    )
    (comp (ref "VT5")
      (value "BD140")
      (footprint "PcbLib_ICs:TO-126 (VERTICAL)")
      (description "General Purpose p-n-p Transistors")
      (fields (field (name "MANUFACTURER") "STMicroelectronics"))
      (libsource (lib "Schlib_STMicroelectronics") (part "BD140"))
    )
    (comp (ref "VT6")
      (value "BD139")
      (footprint "PcbLib_ICs:TO-126 (VERTICAL)")
      (description "General Purpose n-p-n Transistors")
      (fields (field (name "MANUFACTURER") "STMicroelectronics"))
      (libsource (lib "Schlib_STMicroelectronics") (part "BD139"))
    )
    (comp (ref "VT7")
      (value "BD140")
      (footprint "PcbLib_ICs:TO-126 (VERTICAL)")
      (description "General Purpose p-n-p Transistors")
      (fields (field (name "MANUFACTURER") "STMicroelectronics"))
      (libsource (lib "Schlib_STMicroelectronics") (part "BD140"))
    )
    (comp (ref "VT8")
      (value "FCH20N60")
      (footprint "PcbLib_ICs:TO-247_with_TO-220 (VERTICAL)")
      (description "600V @ 20A N-Channel MOSFET")
      (fields (field (name "MANUFACTURER") "ON Semiconductor"))
      (libsource (lib "Schlib_ONSemiconductor") (part "FCH20N60"))
    )
    (comp (ref "VT9")
      (value "FCH20N60")
      (footprint "PcbLib_ICs:TO-247_with_TO-220 (VERTICAL)")
      (description "600V @ 20A N-Channel MOSFET")
      (fields (field (name "MANUFACTURER") "ON Semiconductor"))
      (libsource (lib "Schlib_ONSemiconductor") (part "FCH20N60"))
    )
    (comp (ref "VT10")
      (value "2SC945")
      (footprint "PcbLib_ICs:TO-92 (VERTICAL,LINE)")
      (description "General Purpose n-p-n Transistors")
      (fields (field (name "MANUFACTURER") "NEC"))
      (libsource (lib "Schlib_NEC") (part "2SC945"))
    )
    (comp (ref "VT11")
      (value "2SA733")
      (footprint "PcbLib_ICs:TO-92 (VERTICAL,LINE)")
      (description "General Purpose p-n-p Transistors")
      (fields (field (name "MANUFACTURER") "NEC"))
      (libsource (lib "Schlib_NEC") (part "2SA733"))
    )
    (comp (ref "VT13")
      (value "2SA733")
      (footprint "PcbLib_ICs:TO-92 (VERTICAL,LINE)")
      (description "General Purpose p-n-p Transistors")
      (fields (field (name "MANUFACTURER") "NEC"))
      (libsource (lib "Schlib_NEC") (part "2SA733"))
    )
    (comp (ref "VT14")
      (value "BD140")
      (footprint "PcbLib_ICs:TO-126 (VERTICAL)")
      (description "General Purpose p-n-p Transistors")
      (fields (field (name "MANUFACTURER") "STMicroelectronics"))
      (libsource (lib "Schlib_STMicroelectronics") (part "BD140"))
    )
    (comp (ref "VT15")
      (value "BD140")
      (footprint "PcbLib_ICs:TO-126 (VERTICAL)")
      (description "General Purpose p-n-p Transistors")
      (fields (field (name "MANUFACTURER") "STMicroelectronics"))
      (libsource (lib "Schlib_STMicroelectronics") (part "BD140"))
    )
    (comp (ref "VT16")
      (value "FQA70N15")
      (footprint "PcbLib_ICs:TO-3PN (VERTICAL)")
      (description "150V @ 70A 28 mΩ N-Channel MOSFET")
      (fields (field (name "MANUFACTURER") "ON Semiconductor"))
      (libsource (lib "Schlib_ONSemiconductor") (part "FQA70N15"))
    )
    (comp (ref "VT17")
      (value "FQA70N15")
      (footprint "PcbLib_ICs:TO-3PN (VERTICAL)")
      (description "150V @ 70A 28 mΩ N-Channel MOSFET")
      (fields (field (name "MANUFACTURER") "ON Semiconductor"))
      (libsource (lib "Schlib_ONSemiconductor") (part "FQA70N15"))
    )
    (comp (ref "VT18")
      (value "BD139")
      (footprint "PcbLib_ICs:TO-126 (VERTICAL)")
      (description "General Purpose n-p-n Transistors")
      (fields (field (name "MANUFACTURER") "STMicroelectronics"))
      (libsource (lib "Schlib_STMicroelectronics") (part "BD139"))
    )
    (comp (ref "VT19")
      (value "BD139")
      (footprint "PcbLib_ICs:TO-126 (VERTICAL)")
      (description "General Purpose n-p-n Transistors")
      (fields (field (name "MANUFACTURER") "STMicroelectronics"))
      (libsource (lib "Schlib_STMicroelectronics") (part "BD139"))
    )
    (comp (ref "XS3")
      (value "DG500-5.08-02P-14")
      (footprint "PcbLib_Connectors:DG500-5.08-02P")
      (description "2-way screw terminal, pitch 200mils (5.08mm)")
      (fields (field (name "MANUFACTURER") "DEGSON"))
      (libsource (lib "Schlib_OtherComponents") (part "DG500-5.08-02P-14"))
    )
    (comp (ref "XS4")
      (value "DG500-5.08-02P-14")
      (footprint "PcbLib_Connectors:DG500-5.08-02P")
      (description "2-way screw terminal, pitch 200mils (5.08mm)")
      (fields (field (name "MANUFACTURER") "DEGSON"))
      (libsource (lib "Schlib_OtherComponents") (part "DG500-5.08-02P-14"))
    )
    (comp (ref "XS5")
      (value "DG340-3.81-02P-12")
      (footprint "PcbLib_Connectors:DG340-3.81-02P")
      (description "2-way screw terminal, pitch 150mils (3.81mm)")
      (fields (field (name "MANUFACTURER") "DEGSON"))
      (libsource (lib "Schlib_OtherComponents") (part "DG340-3.81-02P-12"))
    )
    (comp (ref "XS6")
      (value "DG340-3.81-02P-12")
      (footprint "PcbLib_Connectors:DG340-3.81-02P")
      (description "2-way screw terminal, pitch 150mils (3.81mm)")
      (fields (field (name "MANUFACTURER") "DEGSON"))
      (libsource (lib "Schlib_OtherComponents") (part "DG340-3.81-02P-12"))
    )
    (comp (ref "XS7")
      (value "DG340-3.81-02P-12")
      (footprint "PcbLib_Connectors:DG340-3.81-02P")
      (description "2-way screw terminal, pitch 150mils (3.81mm)")
      (fields (field (name "MANUFACTURER") "DEGSON"))
      (libsource (lib "Schlib_OtherComponents") (part "DG340-3.81-02P-12"))
    )
  )
  (nets
    (net (code "1") (name "/0V") (class "Default")
      (node (ref "C53") (pin "1") (pinfunction "1_1") (pintype "passive"))
      (node (ref "R55") (pin "2") (pinfunction "2_2") (pintype "passive"))
      (node (ref "R56") (pin "1") (pinfunction "1_1") (pintype "passive"))
      (node (ref "R57") (pin "2") (pinfunction "2_2") (pintype "passive"))
      (node (ref "R69") (pin "2") (pinfunction "2_2") (pintype "passive"))
      (node (ref "XS4") (pin "1") (pinfunction "1_1") (pintype "passive"))
      (node (ref "XS4") (pin "2") (pinfunction "2_2") (pintype "passive"))
    )
    (net (code "2") (name "/ALERT_ISO") (class "Default")
      (node (ref "DA11") (pin "4") (pinfunction "COLLECTOR_4") (pintype "passive"))
      (node (ref "R65") (pin "2") (pinfunction "2_2") (pintype "passive"))
      (node (ref "XS7") (pin "1") (pinfunction "1_1") (pintype "passive"))
    )
    (net (code "3") (name "/CLR_ALERT_ISO") (class "Default")
      (node (ref "R76") (pin "2") (pinfunction "2_2") (pintype "passive"))
      (node (ref "XS6") (pin "2") (pinfunction "2_2") (pintype "passive"))
    )
    (net (code "4") (name "/DAC_VSET") (class "Default")
      (node (ref "DA10") (pin "2") (pinfunction "1IN-_2") (pintype "input"))
      (node (ref "XS5") (pin "1") (pinfunction "1_1") (pintype "passive"))
    )
    (net (code "5") (name "/HALF_OFF_ISO") (class "Default")
      (node (ref "R52") (pin "2") (pinfunction "2_2") (pintype "passive"))
      (node (ref "XS6") (pin "1") (pinfunction "1_1") (pintype "passive"))
    )
    (net (code "6") (name "/HALF_VS") (class "Default")
      (node (ref "C39") (pin "1") (pinfunction "1_1") (pintype "passive"))
      (node (ref "R36") (pin "1") (pinfunction "1_1") (pintype "passive"))
      (node (ref "R40") (pin "1") (pinfunction "1_1") (pintype "passive"))
      (node (ref "R44") (pin "2") (pinfunction "2_2") (pintype "passive"))
      (node (ref "T2") (pin "5") (pinfunction "5_5") (pintype "passive"))
      (node (ref "VD15") (pin "2") (pinfunction "A_2") (pintype "passive"))
      (node (ref "VT5") (pin "2") (pinfunction "C_2") (pintype "passive"))
      (node (ref "VT8") (pin "3") (pinfunction "S_3") (pintype "passive"))
      (node (ref "VT9") (pin "2") (pinfunction "D_2") (pintype "passive"))
    )
    (net (code "7") (name "/VOUT") (class "Default")
      (node (ref "C44") (pin "2") (pinfunction "2_2") (pintype "passive"))
      (node (ref "C45") (pin "1") (pinfunction "1_1") (pintype "passive"))
      (node (ref "C46") (pin "2") (pinfunction "2_2") (pintype "passive"))
      (node (ref "C47") (pin "1") (pinfunction "1_1") (pintype "passive"))
      (node (ref "C50") (pin "2") (pinfunction "2_2") (pintype "passive"))
      (node (ref "C51") (pin "1") (pinfunction "1_1") (pintype "passive"))
      (node (ref "C52") (pin "1") (pinfunction "1_1") (pintype "passive"))
      (node (ref "C53") (pin "2") (pinfunction "2_2") (pintype "passive"))
      (node (ref "L10") (pin "2") (pinfunction "2_2") (pintype "passive"))
      (node (ref "R56") (pin "2") (pinfunction "2_2") (pintype "passive"))
      (node (ref "XS3") (pin "1") (pinfunction "1_1") (pintype "passive"))
      (node (ref "XS3") (pin "2") (pinfunction "2_2") (pintype "passive"))
    )
    (net (code "8") (name "CLR_ALERT") (class "Default")
      (node (ref "DA9") (pin "4") (pinfunction "COLLECTOR_4") (pintype "passive"))
      (node (ref "KT7") (pin "1") (pinfunction "1_1") (pintype "passive"))
      (node (ref "R51") (pin "2") (pinfunction "2_2") (pintype "passive"))
    )
    (net (code "9") (name "FB_VOLTAGE") (class "Default")
      (node (ref "DA7") (pin "6") (pinfunction "COLLECTOR2_6") (pintype "passive"))
      (node (ref "KT5") (pin "1") (pinfunction "1_1") (pintype "passive"))
      (node (ref "R49") (pin "2") (pinfunction "2_2") (pintype "passive"))
    )
    (net (code "10") (name "GND") (class "Default")
      (node (ref "C44") (pin "1") (pinfunction "1_1") (pintype "passive"))
      (node (ref "C45") (pin "2") (pinfunction "2_2") (pintype "passive"))
      (node (ref "C46") (pin "1") (pinfunction "1_1") (pintype "passive"))
      (node (ref "C47") (pin "2") (pinfunction "2_2") (pintype "passive"))
      (node (ref "C48") (pin "2") (pinfunction "2_2") (pintype "passive"))
      (node (ref "C49") (pin "2") (pinfunction "2_2") (pintype "passive"))
      (node (ref "C50") (pin "1") (pinfunction "1_1") (pintype "passive"))
      (node (ref "C51") (pin "2") (pinfunction "2_2") (pintype "passive"))
      (node (ref "C52") (pin "2") (pinfunction "2_2") (pintype "passive"))
      (node (ref "C61") (pin "2") (pinfunction "2_2") (pintype "passive"))
      (node (ref "C62") (pin "2") (pinfunction "2_2") (pintype "passive"))
      (node (ref "DA10") (pin "4") (pinfunction "V-_4") (pintype "power_in"))
      (node (ref "DA11") (pin "3") (pinfunction "EMITTER_3") (pintype "passive"))
      (node (ref "DA12") (pin "3") (pinfunction "1IN+_3") (pintype "input"))
      (node (ref "DA12") (pin "4") (pinfunction "GND_4") (pintype "power_in"))
      (node (ref "DA12") (pin "5") (pinfunction "2IN+_5") (pintype "input"))
      (node (ref "DA5") (pin "4") (pinfunction "V-_4") (pintype "power_in"))
      (node (ref "DA6") (pin "2") (pinfunction "CATHODE_2") (pintype "power_in"))
      (node (ref "DA7") (pin "3") (pinfunction "EMITTER1_3") (pintype "passive"))
      (node (ref "DA7") (pin "4") (pinfunction "CATHODE2_4") (pintype "power_in"))
      (node (ref "DD1") (pin "7") (pinfunction "GND_7") (pintype "power_in"))
      (node (ref "R48") (pin "1") (pinfunction "1_1") (pintype "passive"))
      (node (ref "R50") (pin "2") (pinfunction "2_2") (pintype "passive"))
      (node (ref "R53") (pin "1") (pinfunction "1_1") (pintype "passive"))
      (node (ref "R55") (pin "1") (pinfunction "1_1") (pintype "passive"))
      (node (ref "R57") (pin "1") (pinfunction "1_1") (pintype "passive"))
      (node (ref "R68") (pin "1") (pinfunction "1_1") (pintype "passive"))
      (node (ref "R73") (pin "1") (pinfunction "1_1") (pintype "passive"))
      (node (ref "R79") (pin "1") (pinfunction "1_1") (pintype "passive"))
      (node (ref "R80") (pin "2") (pinfunction "2_2") (pintype "passive"))
      (node (ref "R83") (pin "1") (pinfunction "1_1") (pintype "passive"))
      (node (ref "R84") (pin "1") (pinfunction "1_1") (pintype "passive"))
      (node (ref "T2") (pin "11") (pinfunction "11_11") (pintype "passive"))
      (node (ref "T2") (pin "12") (pinfunction "12_12") (pintype "passive"))
      (node (ref "VD16") (pin "1") (pinfunction "1_1") (pintype "passive"))
      (node (ref "VD17") (pin "1") (pinfunction "1_1") (pintype "passive"))
      (node (ref "VT10") (pin "3") (pinfunction "E_3") (pintype "passive"))
      (node (ref "VT14") (pin "2") (pinfunction "C_2") (pintype "passive"))
      (node (ref "VT15") (pin "2") (pinfunction "C_2") (pintype "passive"))
      (node (ref "XS5") (pin "2") (pinfunction "2_2") (pintype "passive"))
      (node (ref "XS7") (pin "2") (pinfunction "2_2") (pintype "passive"))
    )
    (net (code "11") (name "HALF_BRIDGE_OFF") (class "Default")
      (node (ref "DA8") (pin "4") (pinfunction "COLLECTOR_4") (pintype "passive"))
      (node (ref "KT16") (pin "1") (pinfunction "1_1") (pintype "passive"))
      (node (ref "R72") (pin "2") (pinfunction "2_2") (pintype "passive"))
    )
    (net (code "12") (name "Net-(C41-Pad2)") (class "Default")
      (node (ref "C41") (pin "2") (pinfunction "2_2") (pintype "passive"))
      (node (ref "C42") (pin "1") (pinfunction "1_1") (pintype "passive"))
      (node (ref "T2") (pin "1") (pinfunction "1_1") (pintype "passive"))
    )
    (net (code "13") (name "Net-(C43-Pad2)") (class "Default")
      (node (ref "C43") (pin "2") (pinfunction "2_2") (pintype "passive"))
      (node (ref "T2") (pin "6") (pinfunction "6_6") (pintype "passive"))
    )
    (net (code "14") (name "Net-(DA5A-1IN+)") (class "Default")
      (node (ref "C64") (pin "1") (pinfunction "1_1") (pintype "passive"))
      (node (ref "DA5") (pin "3") (pinfunction "1IN+_3") (pintype "input"))
      (node (ref "R70") (pin "1") (pinfunction "1_1") (pintype "passive"))
    )
    (net (code "15") (name "Net-(DA5A-1IN-)") (class "Default")
      (node (ref "C64") (pin "2") (pinfunction "2_2") (pintype "passive"))
      (node (ref "DA5") (pin "2") (pinfunction "1IN-_2") (pintype "input"))
      (node (ref "R45") (pin "1") (pinfunction "1_1") (pintype "passive"))
      (node (ref "R71") (pin "2") (pinfunction "2_2") (pintype "passive"))
    )
    (net (code "16") (name "Net-(DA5A-V+)") (class "Default")
      (node (ref "C37") (pin "1") (pinfunction "1_1") (pintype "passive"))
      (node (ref "C38") (pin "1") (pinfunction "1_1") (pintype "passive"))
      (node (ref "DA5") (pin "8") (pinfunction "V+_8") (pintype "power_in"))
      (node (ref "L9") (pin "1") (pinfunction "1_1") (pintype "passive"))
    )
    (net (code "17") (name "Net-(DA6-ANODE)") (class "Default")
      (node (ref "DA6") (pin "1") (pinfunction "ANODE_1") (pintype "passive"))
      (node (ref "R48") (pin "2") (pinfunction "2_2") (pintype "passive"))
      (node (ref "R64") (pin "1") (pinfunction "1_1") (pintype "passive"))
    )
    (net (code "18") (name "Net-(DA7A-ANODE1)") (class "Default")
      (node (ref "DA7") (pin "1") (pinfunction "ANODE1_1") (pintype "passive"))
      (node (ref "R54") (pin "1") (pinfunction "1_1") (pintype "passive"))
    )
    (net (code "19") (name "Net-(DA7A-CATHODE1)") (class "Default")
      (node (ref "DA7") (pin "2") (pinfunction "CATHODE1_2") (pintype "power_in"))
      (node (ref "DA7") (pin "3") (pinfunction "ANODE2_3") (pintype "passive"))
    )
    (net (code "20") (name "Net-(DA8-ANODE)") (class "Default")
      (node (ref "DA8") (pin "1") (pinfunction "ANODE_1") (pintype "passive"))
      (node (ref "R46") (pin "2") (pinfunction "2_2") (pintype "passive"))
    )
    (net (code "21") (name "Net-(DA8-CATHODE)") (class "Default")
      (node (ref "DA8") (pin "2") (pinfunction "CATHODE_2") (pintype "power_in"))
      (node (ref "VT10") (pin "2") (pinfunction "C_2") (pintype "passive"))
    )
    (net (code "22") (name "Net-(DA9-ANODE)") (class "Default")
      (node (ref "DA9") (pin "1") (pinfunction "ANODE_1") (pintype "passive"))
      (node (ref "VT13") (pin "2") (pinfunction "C_2") (pintype "passive"))
    )
    (net (code "23") (name "Net-(DA9-CATHODE)") (class "Default")
      (node (ref "DA9") (pin "2") (pinfunction "CATHODE_2") (pintype "power_in"))
      (node (ref "R73") (pin "2") (pinfunction "2_2") (pintype "passive"))
    )
    (net (code "24") (name "Net-(DA10A-1IN+)") (class "Default")
      (node (ref "DA10") (pin "3") (pinfunction "1IN+_3") (pintype "input"))
      (node (ref "DA7") (pin "4") (pinfunction "COLLECTOR1_4") (pintype "passive"))
      (node (ref "R67") (pin "2") (pinfunction "2_2") (pintype "passive"))
    )
    (net (code "25") (name "Net-(DA10A-1OUT)") (class "Default")
      (node (ref "DA10") (pin "1") (pinfunction "1OUT_1") (pintype "output"))
      (node (ref "R54") (pin "2") (pinfunction "2_2") (pintype "passive"))
    )
    (net (code "26") (name "Net-(DA10A-V+)") (class "Default")
      (node (ref "C61") (pin "1") (pinfunction "1_1") (pintype "passive"))
      (node (ref "C62") (pin "1") (pinfunction "1_1") (pintype "passive"))
      (node (ref "DA10") (pin "8") (pinfunction "V+_8") (pintype "power_in"))
      (node (ref "L12") (pin "1") (pinfunction "1_1") (pintype "passive"))
      (node (ref "R67") (pin "1") (pinfunction "1_1") (pintype "passive"))
    )
    (net (code "27") (name "Net-(DA10B-2IN+)") (class "Default")
      (node (ref "C63") (pin "1") (pinfunction "1_1") (pintype "passive"))
      (node (ref "DA10") (pin "5") (pinfunction "2IN+_5") (pintype "input"))
      (node (ref "R69") (pin "1") (pinfunction "1_1") (pintype "passive"))
    )
    (net (code "28") (name "Net-(DA10B-2IN-)") (class "Default")
      (node (ref "C63") (pin "2") (pinfunction "2_2") (pintype "passive"))
      (node (ref "DA10") (pin "6") (pinfunction "2IN-_6") (pintype "input"))
      (node (ref "R66") (pin "1") (pinfunction "1_1") (pintype "passive"))
      (node (ref "R68") (pin "2") (pinfunction "2_2") (pintype "passive"))
    )
    (net (code "29") (name "Net-(DA10B-2OUT)") (class "Default")
      (node (ref "DA10") (pin "7") (pinfunction "2OUT_7") (pintype "output"))
      (node (ref "R64") (pin "2") (pinfunction "2_2") (pintype "passive"))
      (node (ref "R66") (pin "2") (pinfunction "2_2") (pintype "passive"))
    )
    (net (code "30") (name "Net-(DA11-ANODE)") (class "Default")
      (node (ref "DA11") (pin "1") (pinfunction "ANODE_1") (pintype "passive"))
      (node (ref "VT11") (pin "2") (pinfunction "C_2") (pintype "passive"))
    )
    (net (code "31") (name "Net-(DA11-CATHODE)") (class "Default")
      (node (ref "DA11") (pin "2") (pinfunction "CATHODE_2") (pintype "power_in"))
      (node (ref "R53") (pin "2") (pinfunction "2_2") (pintype "passive"))
    )
    (net (code "32") (name "Net-(DA12A-1IN-)") (class "Default")
      (node (ref "DA12") (pin "2") (pinfunction "1IN-_2") (pintype "input"))
      (node (ref "R77") (pin "1") (pinfunction "1_1") (pintype "passive"))
      (node (ref "VD16") (pin "2") (pinfunction "2_2") (pintype "passive"))
    )
    (net (code "33") (name "Net-(DA12A-1OUT)") (class "Default")
      (node (ref "DA12") (pin "1") (pinfunction "1OUT_1") (pintype "output"))
      (node (ref "DD1") (pin "1") (pinfunction "A0_1") (pintype "input"))
      (node (ref "DD1") (pin "6") (pinfunction "B1_6") (pintype "input"))
      (node (ref "R79") (pin "2") (pinfunction "2_2") (pintype "passive"))
    )
    (net (code "34") (name "Net-(DA12B-2IN-)") (class "Default")
      (node (ref "DA12") (pin "6") (pinfunction "2IN-_6") (pintype "input"))
      (node (ref "R78") (pin "2") (pinfunction "2_2") (pintype "passive"))
      (node (ref "VD17") (pin "2") (pinfunction "2_2") (pintype "passive"))
    )
    (net (code "35") (name "Net-(DA12B-2OUT)") (class "Default")
      (node (ref "DA12") (pin "7") (pinfunction "2OUT_7") (pintype "output"))
      (node (ref "DD1") (pin "2") (pinfunction "B0_2") (pintype "input"))
      (node (ref "DD1") (pin "9") (pinfunction "B2_9") (pintype "input"))
      (node (ref "R80") (pin "1") (pinfunction "1_1") (pintype "passive"))
    )
    (net (code "36") (name "Net-(DD1A-Y0)") (class "Default")
      (node (ref "DD1") (pin "12") (pinfunction "A3_12") (pintype "input"))
      (node (ref "DD1") (pin "3") (pinfunction "Y0_3") (pintype "output"))
    )
    (net (code "37") (name "Net-(DD1B-A1)") (class "Default")
      (node (ref "DD1") (pin "11") (pinfunction "Y3_11") (pintype "output"))
      (node (ref "DD1") (pin "5") (pinfunction "A1_5") (pintype "input"))
      (node (ref "DD1") (pin "8") (pinfunction "A2_8") (pintype "input"))
    )
    (net (code "38") (name "Net-(DD1B-Y1)") (class "Default")
      (node (ref "DD1") (pin "4") (pinfunction "Y1_4") (pintype "output"))
      (node (ref "R83") (pin "2") (pinfunction "2_2") (pintype "passive"))
      (node (ref "VT14") (pin "1") (pinfunction "B_1") (pintype "passive"))
      (node (ref "VT18") (pin "1") (pinfunction "B_1") (pintype "passive"))
    )
    (net (code "39") (name "Net-(DD1C-Y2)") (class "Default")
      (node (ref "DD1") (pin "10") (pinfunction "Y2_10") (pintype "output"))
      (node (ref "R84") (pin "2") (pinfunction "2_2") (pintype "passive"))
      (node (ref "VT15") (pin "1") (pinfunction "B_1") (pintype "passive"))
      (node (ref "VT19") (pin "1") (pinfunction "B_1") (pintype "passive"))
    )
    (net (code "40") (name "Net-(T2-Pad10)") (class "Default")
      (node (ref "T2") (pin "10") (pinfunction "10_10") (pintype "passive"))
      (node (ref "T2") (pin "9") (pinfunction "9_9") (pintype "passive"))
    )
    (net (code "41") (name "Net-(T2-Pad13)") (class "Default")
      (node (ref "T2") (pin "13") (pinfunction "13_13") (pintype "passive"))
      (node (ref "T2") (pin "14") (pinfunction "14_14") (pintype "passive"))
    )
    (net (code "42") (name "Net-(VD14-C)") (class "Default")
      (node (ref "C39") (pin "2") (pinfunction "2_2") (pintype "passive"))
      (node (ref "R43") (pin "1") (pinfunction "1_1") (pintype "passive"))
      (node (ref "VD14") (pin "1") (pinfunction "C_1") (pintype "passive"))
    )
    (net (code "43") (name "Net-(VD15-C)") (class "Default")
      (node (ref "C40") (pin "2") (pinfunction "2_2") (pintype "passive"))
      (node (ref "R44") (pin "1") (pinfunction "1_1") (pintype "passive"))
      (node (ref "VD15") (pin "1") (pinfunction "C_1") (pintype "passive"))
    )
    (net (code "44") (name "Net-(VT4-B)") (class "Default")
      (node (ref "R34") (pin "1") (pinfunction "1_1") (pintype "passive"))
      (node (ref "R36") (pin "2") (pinfunction "2_2") (pintype "passive"))
      (node (ref "VT4") (pin "1") (pinfunction "B_1") (pintype "passive"))
      (node (ref "VT5") (pin "1") (pinfunction "B_1") (pintype "passive"))
    )
    (net (code "45") (name "Net-(VT4-E)") (class "Default")
      (node (ref "R38") (pin "2") (pinfunction "2_2") (pintype "passive"))
      (node (ref "VD12") (pin "1") (pinfunction "1_1") (pintype "passive"))
      (node (ref "VT4") (pin "3") (pinfunction "E_3") (pintype "passive"))
      (node (ref "VT5") (pin "3") (pinfunction "E_3") (pintype "passive"))
    )
    (net (code "46") (name "Net-(VT6-B)") (class "Default")
      (node (ref "R35") (pin "1") (pinfunction "1_1") (pintype "passive"))
      (node (ref "R37") (pin "2") (pinfunction "2_2") (pintype "passive"))
      (node (ref "VT6") (pin "1") (pinfunction "B_1") (pintype "passive"))
      (node (ref "VT7") (pin "1") (pinfunction "B_1") (pintype "passive"))
    )
    (net (code "47") (name "Net-(VT6-E)") (class "Default")
      (node (ref "R39") (pin "2") (pinfunction "2_2") (pintype "passive"))
      (node (ref "VD13") (pin "1") (pinfunction "1_1") (pintype "passive"))
      (node (ref "VT6") (pin "3") (pinfunction "E_3") (pintype "passive"))
      (node (ref "VT7") (pin "3") (pinfunction "E_3") (pintype "passive"))
    )
    (net (code "48") (name "Net-(VT8-G)") (class "Default")
      (node (ref "R38") (pin "1") (pinfunction "1_1") (pintype "passive"))
      (node (ref "R40") (pin "2") (pinfunction "2_2") (pintype "passive"))
      (node (ref "VD12") (pin "2") (pinfunction "2_2") (pintype "passive"))
      (node (ref "VT8") (pin "1") (pinfunction "G_1") (pintype "passive"))
    )
    (net (code "49") (name "Net-(VT9-G)") (class "Default")
      (node (ref "R39") (pin "1") (pinfunction "1_1") (pintype "passive"))
      (node (ref "R41") (pin "2") (pinfunction "2_2") (pintype "passive"))
      (node (ref "VD13") (pin "2") (pinfunction "2_2") (pintype "passive"))
      (node (ref "VT9") (pin "1") (pinfunction "G_1") (pintype "passive"))
    )
    (net (code "50") (name "Net-(VT9-S)") (class "Default")
      (node (ref "R42") (pin "2") (pinfunction "2_2") (pintype "passive"))
      (node (ref "R70") (pin "2") (pinfunction "2_2") (pintype "passive"))
      (node (ref "VT9") (pin "3") (pinfunction "S_3") (pintype "passive"))
    )
    (net (code "51") (name "Net-(VT10-B)") (class "Default")
      (node (ref "R50") (pin "1") (pinfunction "1_1") (pintype "passive"))
      (node (ref "R52") (pin "1") (pinfunction "1_1") (pintype "passive"))
      (node (ref "VT10") (pin "1") (pinfunction "B_1") (pintype "passive"))
    )
    (net (code "52") (name "Net-(VT11-B)") (class "Default")
      (node (ref "R47") (pin "1") (pinfunction "1_1") (pintype "passive"))
      (node (ref "R75") (pin "2") (pinfunction "2_2") (pintype "passive"))
      (node (ref "VT11") (pin "1") (pinfunction "B_1") (pintype "passive"))
    )
    (net (code "53") (name "Net-(VT13-B)") (class "Default")
      (node (ref "R74") (pin "1") (pinfunction "1_1") (pintype "passive"))
      (node (ref "R76") (pin "1") (pinfunction "1_1") (pintype "passive"))
      (node (ref "VT13") (pin "1") (pinfunction "B_1") (pintype "passive"))
    )
    (net (code "54") (name "Net-(VT14-E)") (class "Default")
      (node (ref "R81") (pin "2") (pinfunction "2_2") (pintype "passive"))
      (node (ref "VT14") (pin "3") (pinfunction "E_3") (pintype "passive"))
      (node (ref "VT18") (pin "3") (pinfunction "E_3") (pintype "passive"))
    )
    (net (code "55") (name "Net-(VT15-E)") (class "Default")
      (node (ref "R82") (pin "2") (pinfunction "2_2") (pintype "passive"))
      (node (ref "VT15") (pin "3") (pinfunction "E_3") (pintype "passive"))
      (node (ref "VT19") (pin "3") (pinfunction "E_3") (pintype "passive"))
    )
    (net (code "56") (name "Net-(VT16-D)") (class "Default")
      (node (ref "R78") (pin "1") (pinfunction "1_1") (pintype "passive"))
      (node (ref "VT16") (pin "2") (pinfunction "D_2") (pintype "passive"))
    )
    (net (code "57") (name "Net-(VT16-G)") (class "Default")
      (node (ref "R82") (pin "1") (pinfunction "1_1") (pintype "passive"))
      (node (ref "VT16") (pin "1") (pinfunction "G_1") (pintype "passive"))
    )
    (net (code "58") (name "Net-(VT17-D)") (class "Default")
      (node (ref "R77") (pin "2") (pinfunction "2_2") (pintype "passive"))
      (node (ref "VT17") (pin "2") (pinfunction "D_2") (pintype "passive"))
    )
    (net (code "59") (name "Net-(VT17-G)") (class "Default")
      (node (ref "R81") (pin "1") (pinfunction "1_1") (pintype "passive"))
      (node (ref "VT17") (pin "1") (pinfunction "G_1") (pintype "passive"))
    )
    (net (code "60") (name "OVER_CURRENT_HALF_BRIDGE") (class "Default")
      (node (ref "DA5") (pin "1") (pinfunction "1OUT_1") (pintype "output"))
      (node (ref "KT12") (pin "1") (pinfunction "1_1") (pintype "passive"))
      (node (ref "R45") (pin "2") (pinfunction "2_2") (pintype "passive"))
    )
    (net (code "61") (name "OVER_CURRENT_RECTIFIER") (class "Default")
      (node (ref "DA6") (pin "4") (pinfunction "COLLECTOR_4") (pintype "passive"))
      (node (ref "KT13") (pin "1") (pinfunction "1_1") (pintype "passive"))
      (node (ref "R63") (pin "2") (pinfunction "2_2") (pintype "passive"))
    )
    (net (code "62") (name "OVER_TEMP_HALF_BRIDGE") (class "Default")
      (node (ref "KT14") (pin "1") (pinfunction "1_1") (pintype "passive"))
    )
    (net (code "63") (name "OVER_TEMP_RECTIFIER") (class "Default")
      (node (ref "KT15") (pin "1") (pinfunction "1_1") (pintype "passive"))
    )
    (net (code "64") (name "PGND") (class "Default")
      (node (ref "C37") (pin "2") (pinfunction "2_2") (pintype "passive"))
      (node (ref "C38") (pin "2") (pinfunction "2_2") (pintype "passive"))
      (node (ref "C40") (pin "1") (pinfunction "1_1") (pintype "passive"))
      (node (ref "C42") (pin "2") (pinfunction "2_2") (pintype "passive"))
      (node (ref "C43") (pin "1") (pinfunction "1_1") (pintype "passive"))
      (node (ref "DA6") (pin "3") (pinfunction "EMITTER_3") (pintype "passive"))
      (node (ref "DA7") (pin "5") (pinfunction "EMITTER2_5") (pintype "passive"))
      (node (ref "DA8") (pin "3") (pinfunction "EMITTER_3") (pintype "passive"))
      (node (ref "DA9") (pin "3") (pinfunction "EMITTER_3") (pintype "passive"))
      (node (ref "KT6") (pin "1") (pinfunction "1_1") (pintype "passive"))
      (node (ref "KT9") (pin "1") (pinfunction "1_1") (pintype "passive"))
      (node (ref "R37") (pin "1") (pinfunction "1_1") (pintype "passive"))
      (node (ref "R41") (pin "1") (pinfunction "1_1") (pintype "passive"))
      (node (ref "R42") (pin "1") (pinfunction "1_1") (pintype "passive"))
      (node (ref "R71") (pin "1") (pinfunction "1_1") (pintype "passive"))
      (node (ref "VT7") (pin "2") (pinfunction "C_2") (pintype "passive"))
    )
    (net (code "65") (name "PWM_ALERT") (class "Default")
      (node (ref "KT8") (pin "1") (pinfunction "1_1") (pintype "passive"))
      (node (ref "R75") (pin "1") (pinfunction "1_1") (pintype "passive"))
    )
    (net (code "66") (name "PWM_H") (class "Default")
      (node (ref "KT3") (pin "1") (pinfunction "1_1") (pintype "passive"))
      (node (ref "R34") (pin "2") (pinfunction "2_2") (pintype "passive"))
    )
    (net (code "67") (name "PWM_L") (class "Default")
      (node (ref "KT2") (pin "1") (pinfunction "1_1") (pintype "passive"))
      (node (ref "R35") (pin "2") (pinfunction "2_2") (pintype "passive"))
    )
    (net (code "68") (name "VCC_380V") (class "Default")
      (node (ref "C41") (pin "1") (pinfunction "1_1") (pintype "passive"))
      (node (ref "R43") (pin "2") (pinfunction "2_2") (pintype "passive"))
      (node (ref "VD14") (pin "2") (pinfunction "A_2") (pintype "passive"))
      (node (ref "VT8") (pin "2") (pinfunction "D_2") (pintype "passive"))
    )
    (net (code "69") (name "VCC_NONISO_12V0P") (class "Default")
      (node (ref "KT1") (pin "1") (pinfunction "1_1") (pintype "passive"))
      (node (ref "L9") (pin "2") (pinfunction "2_2") (pintype "passive"))
      (node (ref "VT4") (pin "2") (pinfunction "C_2") (pintype "passive"))
      (node (ref "VT6") (pin "2") (pinfunction "C_2") (pintype "passive"))
    )
    (net (code "70") (name "VCC_STANDBY_12V0P") (class "Default")
      (node (ref "C48") (pin "1") (pinfunction "1_1") (pintype "passive"))
      (node (ref "C49") (pin "1") (pinfunction "1_1") (pintype "passive"))
      (node (ref "DA12") (pin "8") (pinfunction "VCC_8") (pintype "power_in"))
      (node (ref "DD1") (pin "13") (pinfunction "B3_13") (pintype "input"))
      (node (ref "DD1") (pin "14") (pinfunction "VCC_14") (pintype "power_in"))
      (node (ref "L12") (pin "2") (pinfunction "2_2") (pintype "passive"))
      (node (ref "R46") (pin "1") (pinfunction "1_1") (pintype "passive"))
      (node (ref "R47") (pin "2") (pinfunction "2_2") (pintype "passive"))
      (node (ref "R49") (pin "1") (pinfunction "1_1") (pintype "passive"))
      (node (ref "R51") (pin "1") (pinfunction "1_1") (pintype "passive"))
      (node (ref "R63") (pin "1") (pinfunction "1_1") (pintype "passive"))
      (node (ref "R65") (pin "1") (pinfunction "1_1") (pintype "passive"))
      (node (ref "R72") (pin "1") (pinfunction "1_1") (pintype "passive"))
      (node (ref "R74") (pin "2") (pinfunction "2_2") (pintype "passive"))
      (node (ref "VT11") (pin "3") (pinfunction "E_3") (pintype "passive"))
      (node (ref "VT13") (pin "3") (pinfunction "E_3") (pintype "passive"))
      (node (ref "VT18") (pin "2") (pinfunction "C_2") (pintype "passive"))
      (node (ref "VT19") (pin "2") (pinfunction "C_2") (pintype "passive"))
    )
    (net (code "71") (name "unconnected-(DA5B-2IN+-Pad5)") (class "Default")
      (node (ref "DA5") (pin "5") (pinfunction "2IN+_5") (pintype "input"))
    )
    (net (code "72") (name "unconnected-(DA5B-2IN--Pad6)") (class "Default")
      (node (ref "DA5") (pin "6") (pinfunction "2IN-_6") (pintype "input"))
    )
    (net (code "73") (name "unconnected-(DA5B-2OUT-Pad7)") (class "Default")
      (node (ref "DA5") (pin "7") (pinfunction "2OUT_7") (pintype "output"))
    )
    (net (code "74") (name "unconnected-(KT4-Pad1)") (class "Default")
      (node (ref "KT4") (pin "1") (pinfunction "1_1") (pintype "passive+no_connect"))
    )
    (net (code "75") (name "unconnected-(KT10-Pad1)") (class "Default")
      (node (ref "KT10") (pin "1") (pinfunction "1_1") (pintype "passive+no_connect"))
    )
    (net (code "76") (name "unconnected-(KT11-Pad1)") (class "Default")
      (node (ref "KT11") (pin "1") (pinfunction "1_1") (pintype "passive+no_connect"))
    )
    (net (code "77") (name "unconnected-(L10-Pad1)") (class "Default")
      (node (ref "L10") (pin "1") (pinfunction "1_1") (pintype "passive"))
    )
    (net (code "78") (name "unconnected-(T2-Pad3)") (class "Default")
      (node (ref "T2") (pin "3") (pinfunction "3_3") (pintype "passive+no_connect"))
    )
    (net (code "79") (name "unconnected-(VT16-S-Pad3)") (class "Default")
      (node (ref "VT16") (pin "3") (pinfunction "S_3") (pintype "passive"))
    )
    (net (code "80") (name "unconnected-(VT17-S-Pad3)") (class "Default")
      (node (ref "VT17") (pin "3") (pinfunction "S_3") (pintype "passive"))
    )
  )
)
